# fpga.net
KiCad netlist of a schematic drawn in EAGLE
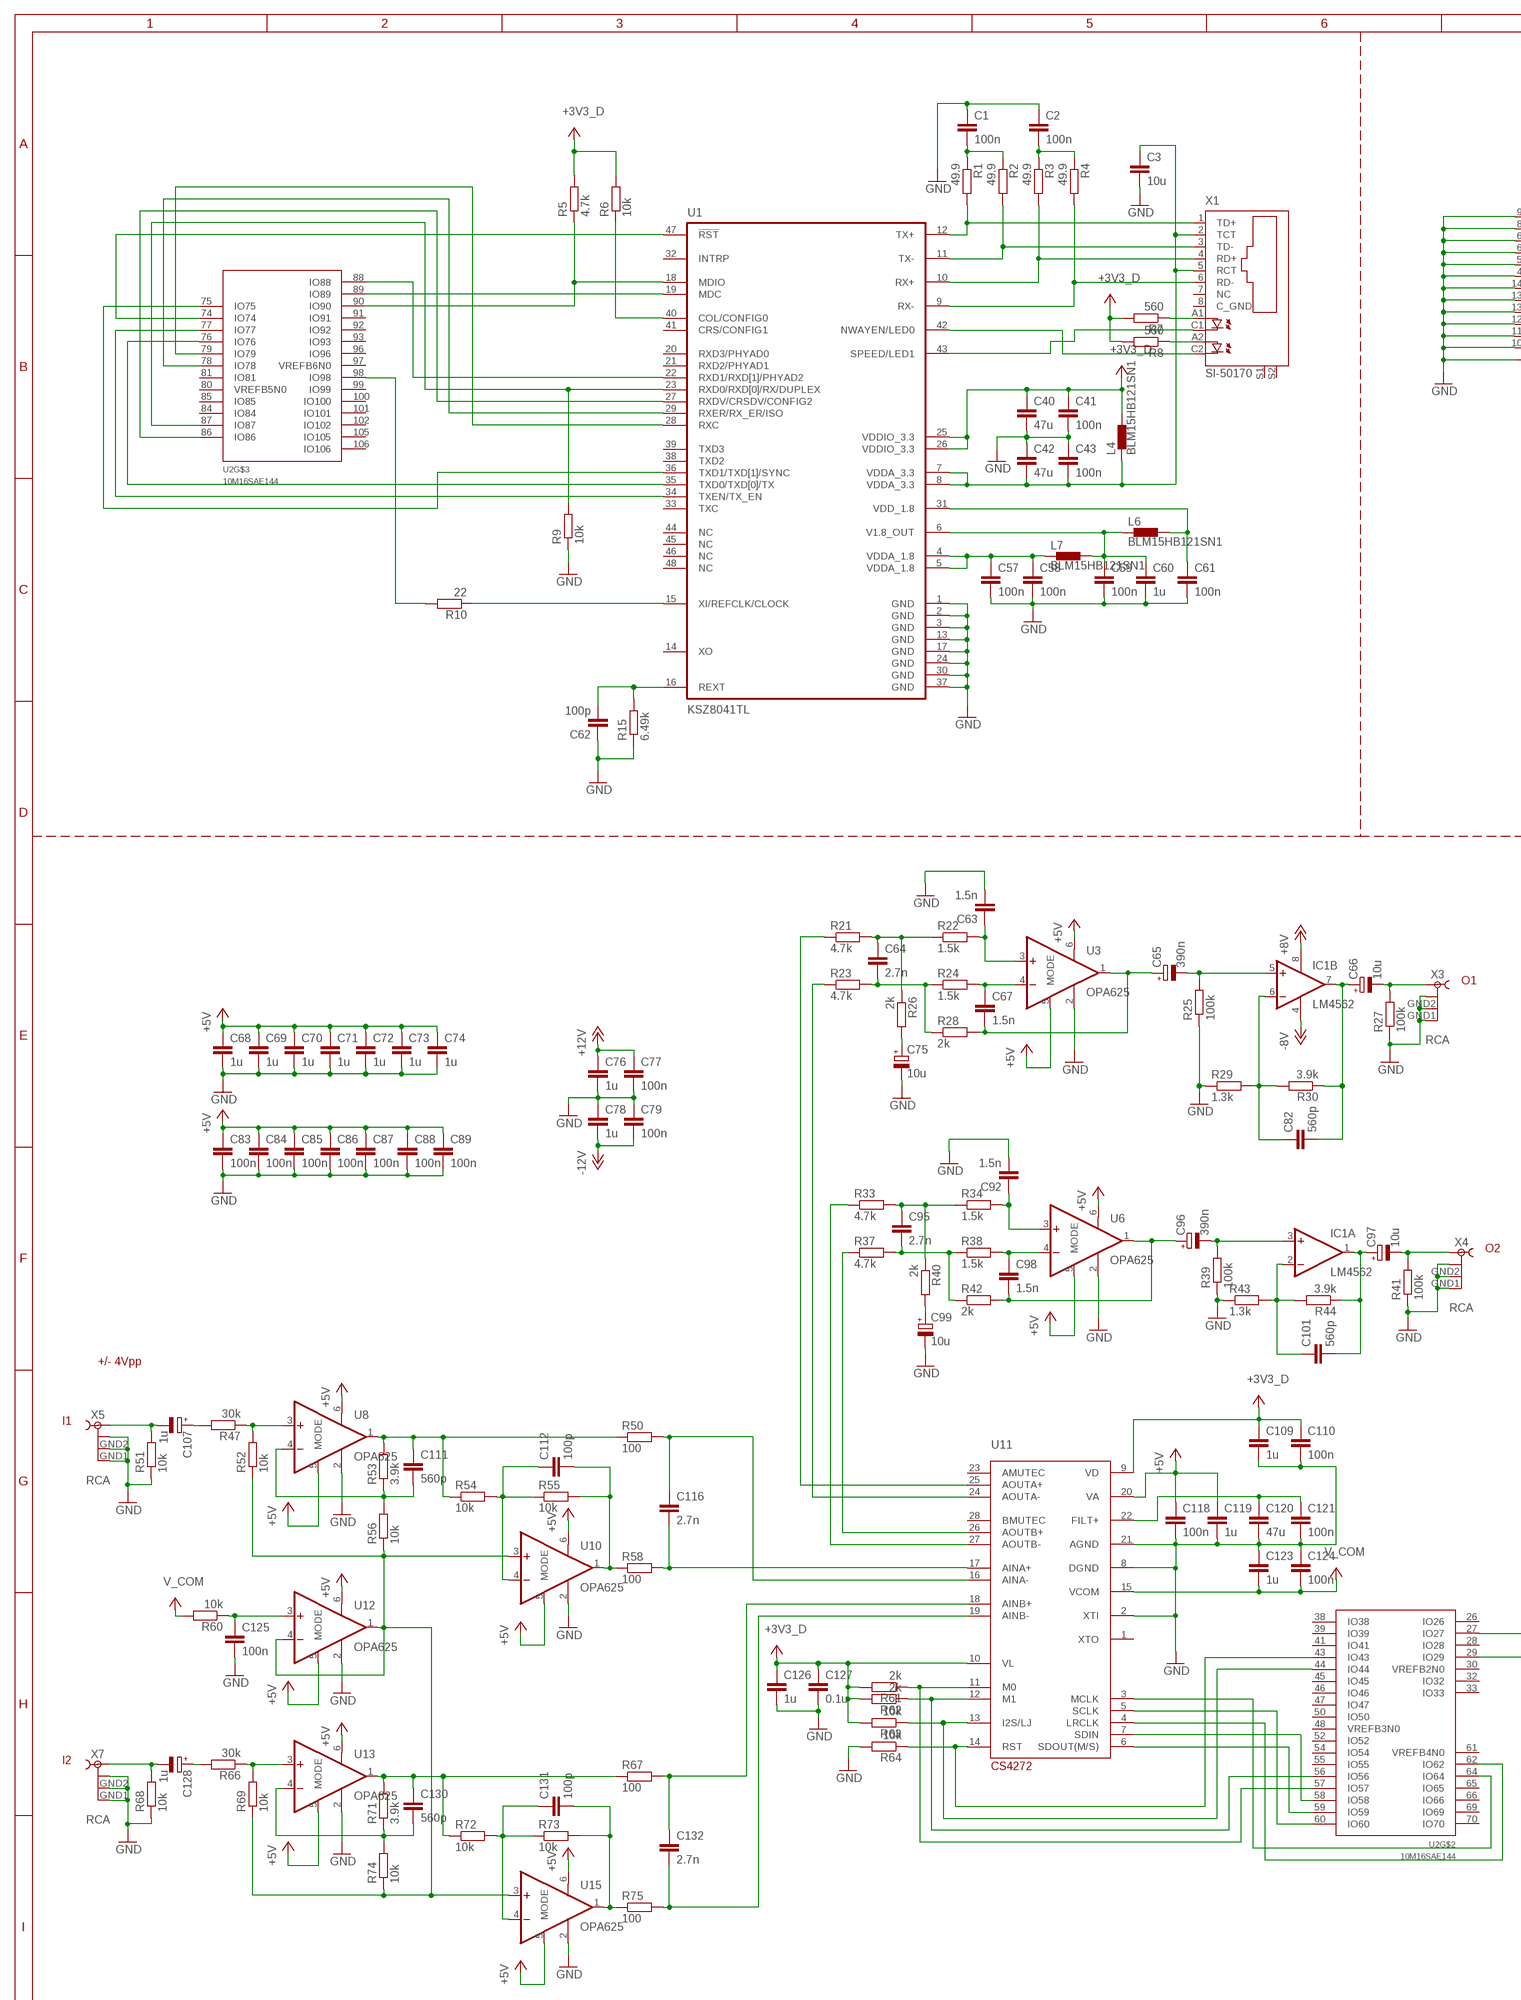
[diagram p0: schematic, sheet 1, part 1 of 2]
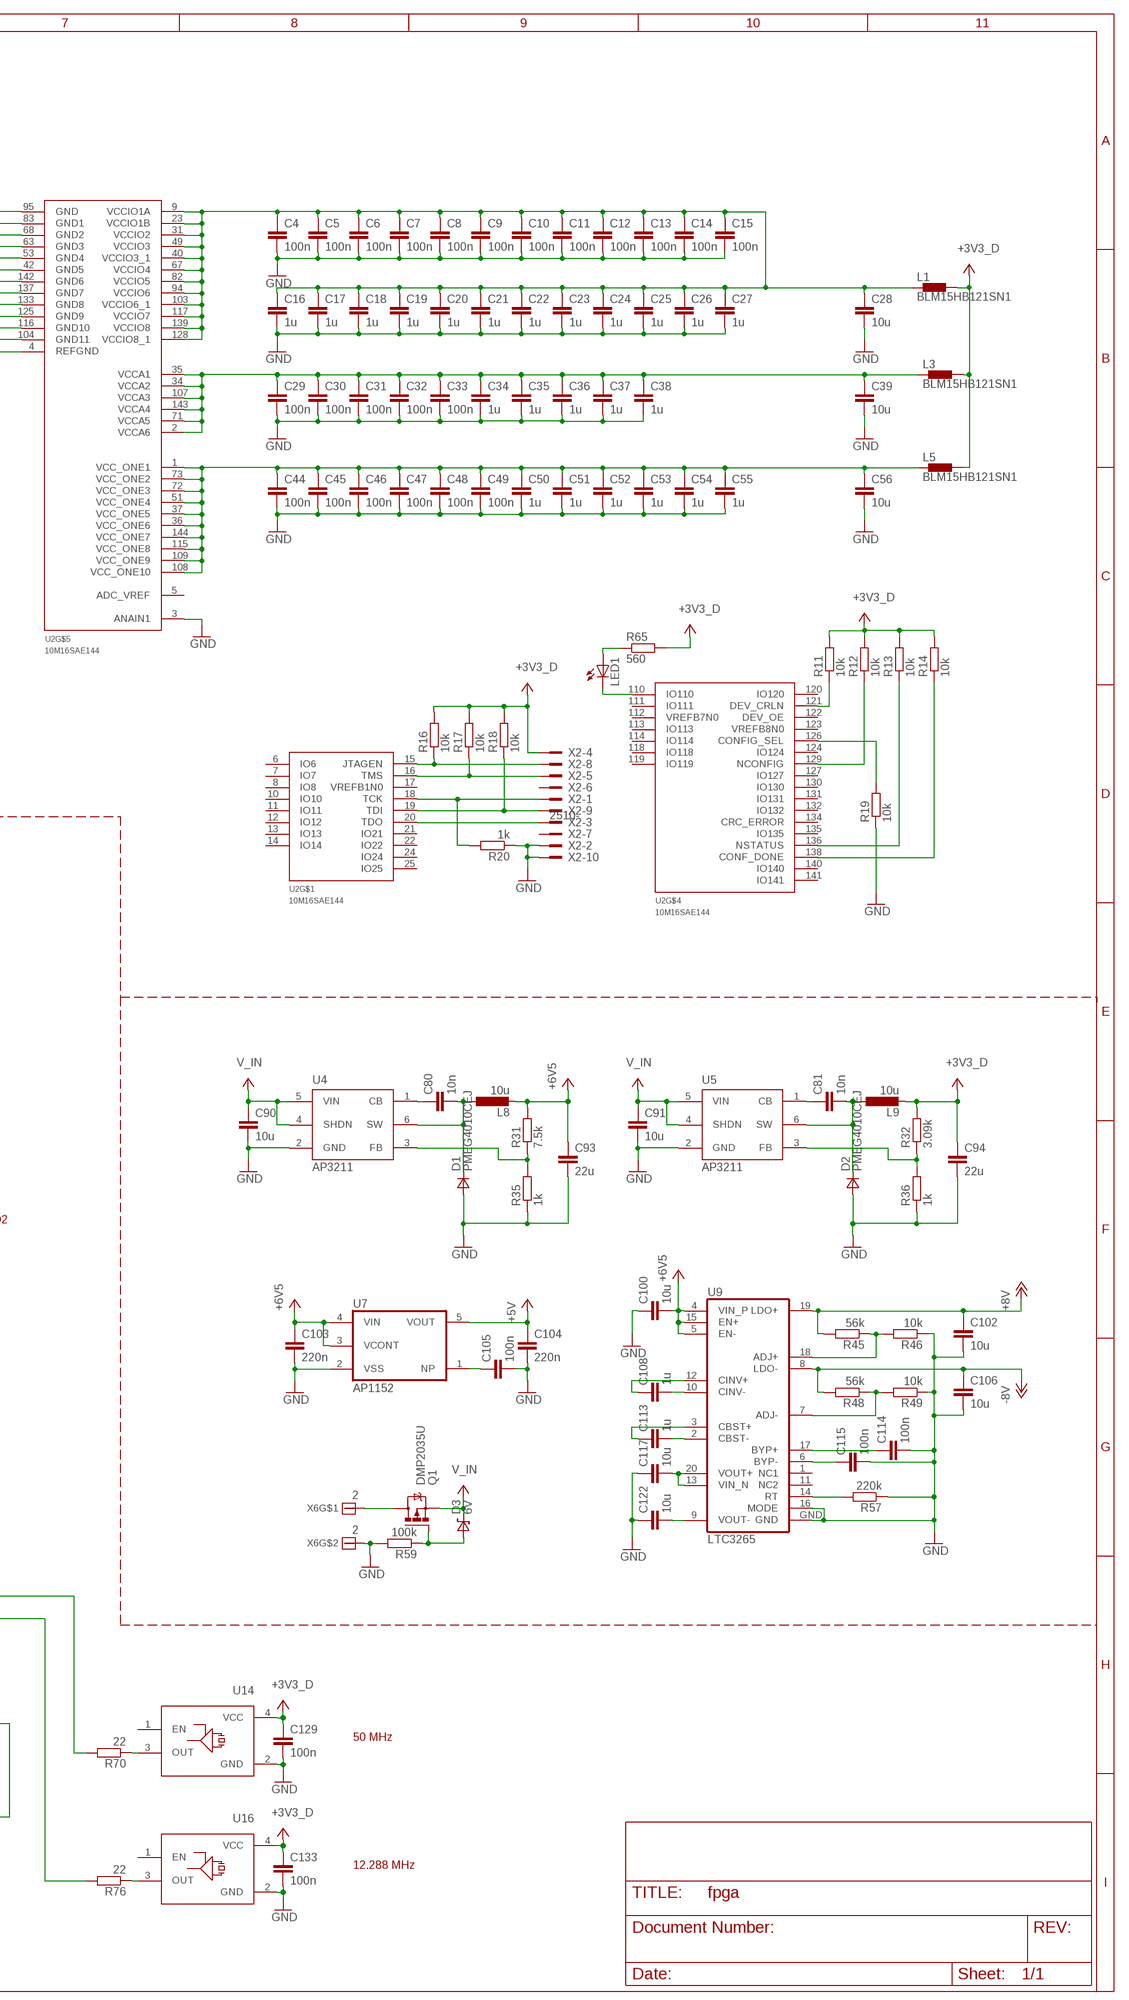
[diagram p1: schematic, sheet 1, part 2 of 2]

(export (version "E")
  (design (tool "Eeschema 10.0.6"))
  (components
    (comp (ref "C1")
      (value "100n")
      (footprint "eagle-import:C0603K")
      (libsource (lib "eagle-import") (part "C-EUC0603K"))
    )
    (comp (ref "C2")
      (value "100n")
      (footprint "eagle-import:C0603K")
      (libsource (lib "eagle-import") (part "C-EUC0603K"))
    )
    (comp (ref "C3")
      (value "10u")
      (footprint "eagle-import:C0805")
      (libsource (lib "eagle-import") (part "C-EUC0805"))
    )
    (comp (ref "C4")
      (value "100n")
      (footprint "eagle-import:C0603K")
      (libsource (lib "eagle-import") (part "C-EUC0603K"))
    )
    (comp (ref "C5")
      (value "100n")
      (footprint "eagle-import:C0603K")
      (libsource (lib "eagle-import") (part "C-EUC0603K"))
    )
    (comp (ref "C6")
      (value "100n")
      (footprint "eagle-import:C0603K")
      (libsource (lib "eagle-import") (part "C-EUC0603K"))
    )
    (comp (ref "C7")
      (value "100n")
      (footprint "eagle-import:C0603K")
      (libsource (lib "eagle-import") (part "C-EUC0603K"))
    )
    (comp (ref "C8")
      (value "100n")
      (footprint "eagle-import:C0603K")
      (libsource (lib "eagle-import") (part "C-EUC0603K"))
    )
    (comp (ref "C9")
      (value "100n")
      (footprint "eagle-import:C0603K")
      (libsource (lib "eagle-import") (part "C-EUC0603K"))
    )
    (comp (ref "C10")
      (value "100n")
      (footprint "eagle-import:C0603K")
      (libsource (lib "eagle-import") (part "C-EUC0603K"))
    )
    (comp (ref "C11")
      (value "100n")
      (footprint "eagle-import:C0603K")
      (libsource (lib "eagle-import") (part "C-EUC0603K"))
    )
    (comp (ref "C12")
      (value "100n")
      (footprint "eagle-import:C0603K")
      (libsource (lib "eagle-import") (part "C-EUC0603K"))
    )
    (comp (ref "C13")
      (value "100n")
      (footprint "eagle-import:C0603K")
      (libsource (lib "eagle-import") (part "C-EUC0603K"))
    )
    (comp (ref "C14")
      (value "100n")
      (footprint "eagle-import:C0603K")
      (libsource (lib "eagle-import") (part "C-EUC0603K"))
    )
    (comp (ref "C15")
      (value "100n")
      (footprint "eagle-import:C0603K")
      (libsource (lib "eagle-import") (part "C-EUC0603K"))
    )
    (comp (ref "C16")
      (value "1u")
      (footprint "eagle-import:C0603K")
      (libsource (lib "eagle-import") (part "C-EUC0603K"))
    )
    (comp (ref "C17")
      (value "1u")
      (footprint "eagle-import:C0603K")
      (libsource (lib "eagle-import") (part "C-EUC0603K"))
    )
    (comp (ref "C18")
      (value "1u")
      (footprint "eagle-import:C0603K")
      (libsource (lib "eagle-import") (part "C-EUC0603K"))
    )
    (comp (ref "C19")
      (value "1u")
      (footprint "eagle-import:C0603K")
      (libsource (lib "eagle-import") (part "C-EUC0603K"))
    )
    (comp (ref "C20")
      (value "1u")
      (footprint "eagle-import:C0603K")
      (libsource (lib "eagle-import") (part "C-EUC0603K"))
    )
    (comp (ref "C21")
      (value "1u")
      (footprint "eagle-import:C0603K")
      (libsource (lib "eagle-import") (part "C-EUC0603K"))
    )
    (comp (ref "C22")
      (value "1u")
      (footprint "eagle-import:C0603K")
      (libsource (lib "eagle-import") (part "C-EUC0603K"))
    )
    (comp (ref "C23")
      (value "1u")
      (footprint "eagle-import:C0603K")
      (libsource (lib "eagle-import") (part "C-EUC0603K"))
    )
    (comp (ref "C24")
      (value "1u")
      (footprint "eagle-import:C0603K")
      (libsource (lib "eagle-import") (part "C-EUC0603K"))
    )
    (comp (ref "C25")
      (value "1u")
      (footprint "eagle-import:C0603K")
      (libsource (lib "eagle-import") (part "C-EUC0603K"))
    )
    (comp (ref "C26")
      (value "1u")
      (footprint "eagle-import:C0603K")
      (libsource (lib "eagle-import") (part "C-EUC0603K"))
    )
    (comp (ref "C27")
      (value "1u")
      (footprint "eagle-import:C0603K")
      (libsource (lib "eagle-import") (part "C-EUC0603K"))
    )
    (comp (ref "C28")
      (value "10u")
      (footprint "eagle-import:C0603K")
      (libsource (lib "eagle-import") (part "C-EUC0603K"))
    )
    (comp (ref "C29")
      (value "100n")
      (footprint "eagle-import:C0603K")
      (libsource (lib "eagle-import") (part "C-EUC0603K"))
    )
    (comp (ref "C30")
      (value "100n")
      (footprint "eagle-import:C0603K")
      (libsource (lib "eagle-import") (part "C-EUC0603K"))
    )
    (comp (ref "C31")
      (value "100n")
      (footprint "eagle-import:C0603K")
      (libsource (lib "eagle-import") (part "C-EUC0603K"))
    )
    (comp (ref "C32")
      (value "100n")
      (footprint "eagle-import:C0603K")
      (libsource (lib "eagle-import") (part "C-EUC0603K"))
    )
    (comp (ref "C33")
      (value "100n")
      (footprint "eagle-import:C0603K")
      (libsource (lib "eagle-import") (part "C-EUC0603K"))
    )
    (comp (ref "C34")
      (value "1u")
      (footprint "eagle-import:C0603K")
      (libsource (lib "eagle-import") (part "C-EUC0603K"))
    )
    (comp (ref "C35")
      (value "1u")
      (footprint "eagle-import:C0603K")
      (libsource (lib "eagle-import") (part "C-EUC0603K"))
    )
    (comp (ref "C36")
      (value "1u")
      (footprint "eagle-import:C0603K")
      (libsource (lib "eagle-import") (part "C-EUC0603K"))
    )
    (comp (ref "C37")
      (value "1u")
      (footprint "eagle-import:C0603K")
      (libsource (lib "eagle-import") (part "C-EUC0603K"))
    )
    (comp (ref "C38")
      (value "1u")
      (footprint "eagle-import:C0603K")
      (libsource (lib "eagle-import") (part "C-EUC0603K"))
    )
    (comp (ref "C39")
      (value "10u")
      (footprint "eagle-import:C0603K")
      (libsource (lib "eagle-import") (part "C-EUC0603K"))
    )
    (comp (ref "C40")
      (value "47u")
      (footprint "eagle-import:C0805")
      (libsource (lib "eagle-import") (part "C-EUC0805"))
    )
    (comp (ref "C41")
      (value "100n")
      (footprint "eagle-import:C0603K")
      (libsource (lib "eagle-import") (part "C-EUC0603K"))
    )
    (comp (ref "C42")
      (value "47u")
      (footprint "eagle-import:C0805")
      (libsource (lib "eagle-import") (part "C-EUC0805"))
    )
    (comp (ref "C43")
      (value "100n")
      (footprint "eagle-import:C0603K")
      (libsource (lib "eagle-import") (part "C-EUC0603K"))
    )
    (comp (ref "C44")
      (value "100n")
      (footprint "eagle-import:C0603K")
      (libsource (lib "eagle-import") (part "C-EUC0603K"))
    )
    (comp (ref "C45")
      (value "100n")
      (footprint "eagle-import:C0603K")
      (libsource (lib "eagle-import") (part "C-EUC0603K"))
    )
    (comp (ref "C46")
      (value "100n")
      (footprint "eagle-import:C0603K")
      (libsource (lib "eagle-import") (part "C-EUC0603K"))
    )
    (comp (ref "C47")
      (value "100n")
      (footprint "eagle-import:C0603K")
      (libsource (lib "eagle-import") (part "C-EUC0603K"))
    )
    (comp (ref "C48")
      (value "100n")
      (footprint "eagle-import:C0603K")
      (libsource (lib "eagle-import") (part "C-EUC0603K"))
    )
    (comp (ref "C49")
      (value "100n")
      (footprint "eagle-import:C0603K")
      (libsource (lib "eagle-import") (part "C-EUC0603K"))
    )
    (comp (ref "C50")
      (value "1u")
      (footprint "eagle-import:C0603K")
      (libsource (lib "eagle-import") (part "C-EUC0603K"))
    )
    (comp (ref "C51")
      (value "1u")
      (footprint "eagle-import:C0603K")
      (libsource (lib "eagle-import") (part "C-EUC0603K"))
    )
    (comp (ref "C52")
      (value "1u")
      (footprint "eagle-import:C0603K")
      (libsource (lib "eagle-import") (part "C-EUC0603K"))
    )
    (comp (ref "C53")
      (value "1u")
      (footprint "eagle-import:C0603K")
      (libsource (lib "eagle-import") (part "C-EUC0603K"))
    )
    (comp (ref "C54")
      (value "1u")
      (footprint "eagle-import:C0603K")
      (libsource (lib "eagle-import") (part "C-EUC0603K"))
    )
    (comp (ref "C55")
      (value "1u")
      (footprint "eagle-import:C0603K")
      (libsource (lib "eagle-import") (part "C-EUC0603K"))
    )
    (comp (ref "C56")
      (value "10u")
      (footprint "eagle-import:C0603K")
      (libsource (lib "eagle-import") (part "C-EUC0603K"))
    )
    (comp (ref "C57")
      (value "100n")
      (footprint "eagle-import:C0603K")
      (libsource (lib "eagle-import") (part "C-EUC0603K"))
    )
    (comp (ref "C58")
      (value "100n")
      (footprint "eagle-import:C0603K")
      (libsource (lib "eagle-import") (part "C-EUC0603K"))
    )
    (comp (ref "C59")
      (value "100n")
      (footprint "eagle-import:C0603K")
      (libsource (lib "eagle-import") (part "C-EUC0603K"))
    )
    (comp (ref "C60")
      (value "1u")
      (footprint "eagle-import:C0603K")
      (libsource (lib "eagle-import") (part "C-EUC0603K"))
    )
    (comp (ref "C61")
      (value "100n")
      (footprint "eagle-import:C0603K")
      (libsource (lib "eagle-import") (part "C-EUC0603K"))
    )
    (comp (ref "C62")
      (value "100p")
      (footprint "eagle-import:C0603K")
      (libsource (lib "eagle-import") (part "C-EUC0603K"))
    )
    (comp (ref "C63")
      (value "1.5n")
      (footprint "eagle-import:C0603K")
      (libsource (lib "eagle-import") (part "C-EUC0603K"))
    )
    (comp (ref "C64")
      (value "2.7n")
      (footprint "eagle-import:C0603K")
      (libsource (lib "eagle-import") (part "C-EUC0603K"))
    )
    (comp (ref "C65")
      (value "390n")
      (footprint "eagle-import:153CLV-0405")
      (libsource (lib "eagle-import") (part "CPOL-EU153CLV-0405"))
    )
    (comp (ref "C66")
      (value "10u")
      (footprint "eagle-import:153CLV-0405")
      (libsource (lib "eagle-import") (part "CPOL-EU153CLV-0405"))
    )
    (comp (ref "C67")
      (value "1.5n")
      (footprint "eagle-import:C0603K")
      (libsource (lib "eagle-import") (part "C-EUC0603K"))
    )
    (comp (ref "C68")
      (value "1u")
      (footprint "eagle-import:C0603K")
      (libsource (lib "eagle-import") (part "C-EUC0603K"))
    )
    (comp (ref "C69")
      (value "1u")
      (footprint "eagle-import:C0603K")
      (libsource (lib "eagle-import") (part "C-EUC0603K"))
    )
    (comp (ref "C70")
      (value "1u")
      (footprint "eagle-import:C0603K")
      (libsource (lib "eagle-import") (part "C-EUC0603K"))
    )
    (comp (ref "C71")
      (value "1u")
      (footprint "eagle-import:C0603K")
      (libsource (lib "eagle-import") (part "C-EUC0603K"))
    )
    (comp (ref "C72")
      (value "1u")
      (footprint "eagle-import:C0603K")
      (libsource (lib "eagle-import") (part "C-EUC0603K"))
    )
    (comp (ref "C73")
      (value "1u")
      (footprint "eagle-import:C0603K")
      (libsource (lib "eagle-import") (part "C-EUC0603K"))
    )
    (comp (ref "C74")
      (value "1u")
      (footprint "eagle-import:C0603K")
      (libsource (lib "eagle-import") (part "C-EUC0603K"))
    )
    (comp (ref "C75")
      (value "10u")
      (footprint "eagle-import:153CLV-0405")
      (libsource (lib "eagle-import") (part "CPOL-EU153CLV-0405"))
    )
    (comp (ref "C76")
      (value "1u")
      (footprint "eagle-import:C0603K")
      (libsource (lib "eagle-import") (part "C-EUC0603K"))
    )
    (comp (ref "C77")
      (value "100n")
      (footprint "eagle-import:C0603K")
      (libsource (lib "eagle-import") (part "C-EUC0603K"))
    )
    (comp (ref "C78")
      (value "1u")
      (footprint "eagle-import:C0603K")
      (libsource (lib "eagle-import") (part "C-EUC0603K"))
    )
    (comp (ref "C79")
      (value "100n")
      (footprint "eagle-import:C0603K")
      (libsource (lib "eagle-import") (part "C-EUC0603K"))
    )
    (comp (ref "C80")
      (value "10n")
      (footprint "eagle-import:C0603K")
      (libsource (lib "eagle-import") (part "C-EUC0603K"))
    )
    (comp (ref "C81")
      (value "10n")
      (footprint "eagle-import:C0603K")
      (libsource (lib "eagle-import") (part "C-EUC0603K"))
    )
    (comp (ref "C82")
      (value "560p")
      (footprint "eagle-import:C0603K")
      (libsource (lib "eagle-import") (part "C-EUC0603K"))
    )
    (comp (ref "C83")
      (value "100n")
      (footprint "eagle-import:C0603K")
      (libsource (lib "eagle-import") (part "C-EUC0603K"))
    )
    (comp (ref "C84")
      (value "100n")
      (footprint "eagle-import:C0603K")
      (libsource (lib "eagle-import") (part "C-EUC0603K"))
    )
    (comp (ref "C85")
      (value "100n")
      (footprint "eagle-import:C0603K")
      (libsource (lib "eagle-import") (part "C-EUC0603K"))
    )
    (comp (ref "C86")
      (value "100n")
      (footprint "eagle-import:C0603K")
      (libsource (lib "eagle-import") (part "C-EUC0603K"))
    )
    (comp (ref "C87")
      (value "100n")
      (footprint "eagle-import:C0603K")
      (libsource (lib "eagle-import") (part "C-EUC0603K"))
    )
    (comp (ref "C88")
      (value "100n")
      (footprint "eagle-import:C0603K")
      (libsource (lib "eagle-import") (part "C-EUC0603K"))
    )
    (comp (ref "C89")
      (value "100n")
      (footprint "eagle-import:C0603K")
      (libsource (lib "eagle-import") (part "C-EUC0603K"))
    )
    (comp (ref "C90")
      (value "10u")
      (footprint "eagle-import:C0805")
      (libsource (lib "eagle-import") (part "C-EUC0805"))
    )
    (comp (ref "C91")
      (value "10u")
      (footprint "eagle-import:C0805")
      (libsource (lib "eagle-import") (part "C-EUC0805"))
    )
    (comp (ref "C92")
      (value "1.5n")
      (footprint "eagle-import:C0603K")
      (libsource (lib "eagle-import") (part "C-EUC0603K"))
    )
    (comp (ref "C93")
      (value "22u")
      (footprint "eagle-import:C1206")
      (libsource (lib "eagle-import") (part "C-EUC1206"))
    )
    (comp (ref "C94")
      (value "22u")
      (footprint "eagle-import:C1206")
      (libsource (lib "eagle-import") (part "C-EUC1206"))
    )
    (comp (ref "C95")
      (value "2.7n")
      (footprint "eagle-import:C0603K")
      (libsource (lib "eagle-import") (part "C-EUC0603K"))
    )
    (comp (ref "C96")
      (value "390n")
      (footprint "eagle-import:153CLV-0405")
      (libsource (lib "eagle-import") (part "CPOL-EU153CLV-0405"))
    )
    (comp (ref "C97")
      (value "10u")
      (footprint "eagle-import:153CLV-0405")
      (libsource (lib "eagle-import") (part "CPOL-EU153CLV-0405"))
    )
    (comp (ref "C98")
      (value "1.5n")
      (footprint "eagle-import:C0603K")
      (libsource (lib "eagle-import") (part "C-EUC0603K"))
    )
    (comp (ref "C99")
      (value "10u")
      (footprint "eagle-import:153CLV-0405")
      (libsource (lib "eagle-import") (part "CPOL-EU153CLV-0405"))
    )
    (comp (ref "C100")
      (value "10u")
      (footprint "eagle-import:C0603K")
      (libsource (lib "eagle-import") (part "C-EUC0603K"))
    )
    (comp (ref "C101")
      (value "560p")
      (footprint "eagle-import:C0603K")
      (libsource (lib "eagle-import") (part "C-EUC0603K"))
    )
    (comp (ref "C102")
      (value "10u")
      (footprint "eagle-import:C0603K")
      (libsource (lib "eagle-import") (part "C-EUC0603K"))
    )
    (comp (ref "C103")
      (value "220n")
      (footprint "eagle-import:C0603K")
      (libsource (lib "eagle-import") (part "C-EUC0603K"))
    )
    (comp (ref "C104")
      (value "220n")
      (footprint "eagle-import:C0603K")
      (libsource (lib "eagle-import") (part "C-EUC0603K"))
    )
    (comp (ref "C105")
      (value "100n")
      (footprint "eagle-import:C0603K")
      (libsource (lib "eagle-import") (part "C-EUC0603K"))
    )
    (comp (ref "C106")
      (value "10u")
      (footprint "eagle-import:C0603K")
      (libsource (lib "eagle-import") (part "C-EUC0603K"))
    )
    (comp (ref "C107")
      (value "1u")
      (footprint "eagle-import:153CLV-0405")
      (libsource (lib "eagle-import") (part "CPOL-EU153CLV-0405"))
    )
    (comp (ref "C108")
      (value "1u")
      (footprint "eagle-import:C0603K")
      (libsource (lib "eagle-import") (part "C-EUC0603K"))
    )
    (comp (ref "C109")
      (value "1u")
      (footprint "eagle-import:C0603K")
      (libsource (lib "eagle-import") (part "C-EUC0603K"))
    )
    (comp (ref "C110")
      (value "100n")
      (footprint "eagle-import:C0603K")
      (libsource (lib "eagle-import") (part "C-EUC0603K"))
    )
    (comp (ref "C111")
      (value "560p")
      (footprint "eagle-import:C0603K")
      (libsource (lib "eagle-import") (part "C-EUC0603K"))
    )
    (comp (ref "C112")
      (value "100p")
      (footprint "eagle-import:C0603K")
      (libsource (lib "eagle-import") (part "C-EUC0603K"))
    )
    (comp (ref "C113")
      (value "1u")
      (footprint "eagle-import:C0603K")
      (libsource (lib "eagle-import") (part "C-EUC0603K"))
    )
    (comp (ref "C114")
      (value "100n")
      (footprint "eagle-import:C0603K")
      (libsource (lib "eagle-import") (part "C-EUC0603K"))
    )
    (comp (ref "C115")
      (value "100n")
      (footprint "eagle-import:C0603K")
      (libsource (lib "eagle-import") (part "C-EUC0603K"))
    )
    (comp (ref "C116")
      (value "2.7n")
      (footprint "eagle-import:C0603K")
      (libsource (lib "eagle-import") (part "C-EUC0603K"))
    )
    (comp (ref "C117")
      (value "10u")
      (footprint "eagle-import:C0603K")
      (libsource (lib "eagle-import") (part "C-EUC0603K"))
    )
    (comp (ref "C118")
      (value "100n")
      (footprint "eagle-import:C0603K")
      (libsource (lib "eagle-import") (part "C-EUC0603K"))
    )
    (comp (ref "C119")
      (value "1u")
      (footprint "eagle-import:C0603K")
      (libsource (lib "eagle-import") (part "C-EUC0603K"))
    )
    (comp (ref "C120")
      (value "47u")
      (footprint "eagle-import:C0805")
      (libsource (lib "eagle-import") (part "C-EUC0805"))
    )
    (comp (ref "C121")
      (value "100n")
      (footprint "eagle-import:C0603K")
      (libsource (lib "eagle-import") (part "C-EUC0603K"))
    )
    (comp (ref "C122")
      (value "10u")
      (footprint "eagle-import:C0603K")
      (libsource (lib "eagle-import") (part "C-EUC0603K"))
    )
    (comp (ref "C123")
      (value "1u")
      (footprint "eagle-import:C0603K")
      (libsource (lib "eagle-import") (part "C-EUC0603K"))
    )
    (comp (ref "C124")
      (value "100n")
      (footprint "eagle-import:C0603K")
      (libsource (lib "eagle-import") (part "C-EUC0603K"))
    )
    (comp (ref "C125")
      (value "100n")
      (footprint "eagle-import:C0603K")
      (libsource (lib "eagle-import") (part "C-EUC0603K"))
    )
    (comp (ref "C126")
      (value "1u")
      (footprint "eagle-import:C0603K")
      (libsource (lib "eagle-import") (part "C-EUC0603K"))
    )
    (comp (ref "C127")
      (value "0.1u")
      (footprint "eagle-import:C0603K")
      (libsource (lib "eagle-import") (part "C-EUC0603K"))
    )
    (comp (ref "C128")
      (value "1u")
      (footprint "eagle-import:153CLV-0405")
      (libsource (lib "eagle-import") (part "CPOL-EU153CLV-0405"))
    )
    (comp (ref "C129")
      (value "100n")
      (footprint "eagle-import:C0603K")
      (libsource (lib "eagle-import") (part "C-EUC0603K"))
    )
    (comp (ref "C130")
      (value "560p")
      (footprint "eagle-import:C0603K")
      (libsource (lib "eagle-import") (part "C-EUC0603K"))
    )
    (comp (ref "C131")
      (value "100p")
      (footprint "eagle-import:C0603K")
      (libsource (lib "eagle-import") (part "C-EUC0603K"))
    )
    (comp (ref "C132")
      (value "2.7n")
      (footprint "eagle-import:C0603K")
      (libsource (lib "eagle-import") (part "C-EUC0603K"))
    )
    (comp (ref "C133")
      (value "100n")
      (footprint "eagle-import:C0603K")
      (libsource (lib "eagle-import") (part "C-EUC0603K"))
    )
    (comp (ref "D1")
      (value "PMEG4010CEJ")
      (footprint "eagle-import:SOD323")
      (fields (field (name "MPN") "CDSOD323-T05C"))
      (libsource (lib "eagle-import") (part "DSOD323"))
    )
    (comp (ref "D2")
      (value "PMEG4010CEJ")
      (footprint "eagle-import:SOD323")
      (fields (field (name "MPN") "CDSOD323-T05C"))
      (libsource (lib "eagle-import") (part "DSOD323"))
    )
    (comp (ref "D3")
      (value "6V")
      (footprint "eagle-import:SOD323")
      (fields (field (name "MPN") "CDSOD323-T05C"))
      (libsource (lib "eagle-import") (part "DSOD323"))
    )
    (comp (ref "IC1")
      (value "LM4562")
      (footprint "eagle-import:SO08")
      (libsource (lib "eagle-import") (part "4558DLM"))
    )
    (comp (ref "L1")
      (value "BLM15HB121SN1")
      (footprint "eagle-import:0402")
      (libsource (lib "eagle-import") (part "BLM15HB121SN1"))
    )
    (comp (ref "L3")
      (value "BLM15HB121SN1")
      (footprint "eagle-import:0402")
      (libsource (lib "eagle-import") (part "BLM15HB121SN1"))
    )
    (comp (ref "L4")
      (value "BLM15HB121SN1")
      (footprint "eagle-import:0402")
      (libsource (lib "eagle-import") (part "BLM15HB121SN1"))
    )
    (comp (ref "L5")
      (value "BLM15HB121SN1")
      (footprint "eagle-import:0402")
      (libsource (lib "eagle-import") (part "BLM15HB121SN1"))
    )
    (comp (ref "L6")
      (value "BLM15HB121SN1")
      (footprint "eagle-import:0402")
      (libsource (lib "eagle-import") (part "BLM15HB121SN1"))
    )
    (comp (ref "L7")
      (value "BLM15HB121SN1")
      (footprint "eagle-import:0402")
      (libsource (lib "eagle-import") (part "BLM15HB121SN1"))
    )
    (comp (ref "L8")
      (value "10u")
      (footprint "eagle-import:AAA")
      (libsource (lib "eagle-import") (part "L-EU"))
    )
    (comp (ref "L9")
      (value "10u")
      (footprint "eagle-import:AAA")
      (libsource (lib "eagle-import") (part "L-EU"))
    )
    (comp (ref "LED1")
      (value "LEDCHIPLED_0603")
      (footprint "eagle-import:CHIPLED_0603")
      (libsource (lib "eagle-import") (part "LEDCHIPLED_0603"))
    )
    (comp (ref "Q1")
      (value "DMP2035U")
      (footprint "eagle-import:MICRO3")
      (libsource (lib "eagle-import") (part "IRLML5203"))
    )
    (comp (ref "R1")
      (value "49.9")
      (footprint "eagle-import:R0603")
      (libsource (lib "eagle-import") (part "R-EU_R0603"))
    )
    (comp (ref "R2")
      (value "49.9")
      (footprint "eagle-import:R0603")
      (libsource (lib "eagle-import") (part "R-EU_R0603"))
    )
    (comp (ref "R3")
      (value "49.9")
      (footprint "eagle-import:R0603")
      (libsource (lib "eagle-import") (part "R-EU_R0603"))
    )
    (comp (ref "R4")
      (value "49.9")
      (footprint "eagle-import:R0603")
      (libsource (lib "eagle-import") (part "R-EU_R0603"))
    )
    (comp (ref "R5")
      (value "4.7k")
      (footprint "eagle-import:R0603")
      (libsource (lib "eagle-import") (part "R-EU_R0603"))
    )
    (comp (ref "R6")
      (value "10k")
      (footprint "eagle-import:R0603")
      (libsource (lib "eagle-import") (part "R-EU_R0603"))
    )
    (comp (ref "R7")
      (value "560")
      (footprint "eagle-import:R0603")
      (libsource (lib "eagle-import") (part "R-EU_R0603"))
    )
    (comp (ref "R8")
      (value "560")
      (footprint "eagle-import:R0603")
      (libsource (lib "eagle-import") (part "R-EU_R0603"))
    )
    (comp (ref "R9")
      (value "10k")
      (footprint "eagle-import:R0603")
      (libsource (lib "eagle-import") (part "R-EU_R0603"))
    )
    (comp (ref "R10")
      (value "22")
      (footprint "eagle-import:R0603")
      (libsource (lib "eagle-import") (part "R-EU_R0603"))
    )
    (comp (ref "R11")
      (value "10k")
      (footprint "eagle-import:R0603")
      (libsource (lib "eagle-import") (part "R-EU_R0603"))
    )
    (comp (ref "R12")
      (value "10k")
      (footprint "eagle-import:R0603")
      (libsource (lib "eagle-import") (part "R-EU_R0603"))
    )
    (comp (ref "R13")
      (value "10k")
      (footprint "eagle-import:R0603")
      (libsource (lib "eagle-import") (part "R-EU_R0603"))
    )
    (comp (ref "R14")
      (value "10k")
      (footprint "eagle-import:R0603")
      (libsource (lib "eagle-import") (part "R-EU_R0603"))
    )
    (comp (ref "R15")
      (value "6.49k")
      (footprint "eagle-import:R0603")
      (libsource (lib "eagle-import") (part "R-EU_R0603"))
    )
    (comp (ref "R16")
      (value "10k")
      (footprint "eagle-import:R0603")
      (libsource (lib "eagle-import") (part "R-EU_R0603"))
    )
    (comp (ref "R17")
      (value "10k")
      (footprint "eagle-import:R0603")
      (libsource (lib "eagle-import") (part "R-EU_R0603"))
    )
    (comp (ref "R18")
      (value "10k")
      (footprint "eagle-import:R0603")
      (libsource (lib "eagle-import") (part "R-EU_R0603"))
    )
    (comp (ref "R19")
      (value "10k")
      (footprint "eagle-import:R0603")
      (libsource (lib "eagle-import") (part "R-EU_R0603"))
    )
    (comp (ref "R20")
      (value "1k")
      (footprint "eagle-import:R0603")
      (libsource (lib "eagle-import") (part "R-EU_R0603"))
    )
    (comp (ref "R21")
      (value "4.7k")
      (footprint "eagle-import:R0603")
      (libsource (lib "eagle-import") (part "R-EU_R0603"))
    )
    (comp (ref "R22")
      (value "1.5k")
      (footprint "eagle-import:R0603")
      (libsource (lib "eagle-import") (part "R-EU_R0603"))
    )
    (comp (ref "R23")
      (value "4.7k")
      (footprint "eagle-import:R0603")
      (libsource (lib "eagle-import") (part "R-EU_R0603"))
    )
    (comp (ref "R24")
      (value "1.5k")
      (footprint "eagle-import:R0603")
      (libsource (lib "eagle-import") (part "R-EU_R0603"))
    )
    (comp (ref "R25")
      (value "100k")
      (footprint "eagle-import:R0603")
      (libsource (lib "eagle-import") (part "R-EU_R0603"))
    )
    (comp (ref "R26")
      (value "2k")
      (footprint "eagle-import:R0603")
      (libsource (lib "eagle-import") (part "R-EU_R0603"))
    )
    (comp (ref "R27")
      (value "100k")
      (footprint "eagle-import:R0603")
      (libsource (lib "eagle-import") (part "R-EU_R0603"))
    )
    (comp (ref "R28")
      (value "2k")
      (footprint "eagle-import:R0603")
      (libsource (lib "eagle-import") (part "R-EU_R0603"))
    )
    (comp (ref "R29")
      (value "1.3k")
      (footprint "eagle-import:R0603")
      (libsource (lib "eagle-import") (part "R-EU_R0603"))
    )
    (comp (ref "R30")
      (value "3.9k")
      (footprint "eagle-import:R0603")
      (libsource (lib "eagle-import") (part "R-EU_R0603"))
    )
    (comp (ref "R31")
      (value "7.5k")
      (footprint "eagle-import:R0603")
      (libsource (lib "eagle-import") (part "R-EU_R0603"))
    )
    (comp (ref "R32")
      (value "3.09k")
      (footprint "eagle-import:R0603")
      (libsource (lib "eagle-import") (part "R-EU_R0603"))
    )
    (comp (ref "R33")
      (value "4.7k")
      (footprint "eagle-import:R0603")
      (libsource (lib "eagle-import") (part "R-EU_R0603"))
    )
    (comp (ref "R34")
      (value "1.5k")
      (footprint "eagle-import:R0603")
      (libsource (lib "eagle-import") (part "R-EU_R0603"))
    )
    (comp (ref "R35")
      (value "1k")
      (footprint "eagle-import:R0603")
      (libsource (lib "eagle-import") (part "R-EU_R0603"))
    )
    (comp (ref "R36")
      (value "1k")
      (footprint "eagle-import:R0603")
      (libsource (lib "eagle-import") (part "R-EU_R0603"))
    )
    (comp (ref "R37")
      (value "4.7k")
      (footprint "eagle-import:R0603")
      (libsource (lib "eagle-import") (part "R-EU_R0603"))
    )
    (comp (ref "R38")
      (value "1.5k")
      (footprint "eagle-import:R0603")
      (libsource (lib "eagle-import") (part "R-EU_R0603"))
    )
    (comp (ref "R39")
      (value "100k")
      (footprint "eagle-import:R0603")
      (libsource (lib "eagle-import") (part "R-EU_R0603"))
    )
    (comp (ref "R40")
      (value "2k")
      (footprint "eagle-import:R0603")
      (libsource (lib "eagle-import") (part "R-EU_R0603"))
    )
    (comp (ref "R41")
      (value "100k")
      (footprint "eagle-import:R0603")
      (libsource (lib "eagle-import") (part "R-EU_R0603"))
    )
    (comp (ref "R42")
      (value "2k")
      (footprint "eagle-import:R0603")
      (libsource (lib "eagle-import") (part "R-EU_R0603"))
    )
    (comp (ref "R43")
      (value "1.3k")
      (footprint "eagle-import:R0603")
      (libsource (lib "eagle-import") (part "R-EU_R0603"))
    )
    (comp (ref "R44")
      (value "3.9k")
      (footprint "eagle-import:R0603")
      (libsource (lib "eagle-import") (part "R-EU_R0603"))
    )
    (comp (ref "R45")
      (value "56k")
      (footprint "eagle-import:R0603")
      (libsource (lib "eagle-import") (part "R-EU_R0603"))
    )
    (comp (ref "R46")
      (value "10k")
      (footprint "eagle-import:R0603")
      (libsource (lib "eagle-import") (part "R-EU_R0603"))
    )
    (comp (ref "R47")
      (value "30k")
      (footprint "eagle-import:R0603")
      (libsource (lib "eagle-import") (part "R-EU_R0603"))
    )
    (comp (ref "R48")
      (value "56k")
      (footprint "eagle-import:R0603")
      (libsource (lib "eagle-import") (part "R-EU_R0603"))
    )
    (comp (ref "R49")
      (value "10k")
      (footprint "eagle-import:R0603")
      (libsource (lib "eagle-import") (part "R-EU_R0603"))
    )
    (comp (ref "R50")
      (value "100")
      (footprint "eagle-import:R0603")
      (libsource (lib "eagle-import") (part "R-EU_R0603"))
    )
    (comp (ref "R51")
      (value "10k")
      (footprint "eagle-import:R0603")
      (libsource (lib "eagle-import") (part "R-EU_R0603"))
    )
    (comp (ref "R52")
      (value "10k")
      (footprint "eagle-import:R0603")
      (libsource (lib "eagle-import") (part "R-EU_R0603"))
    )
    (comp (ref "R53")
      (value "3.9k")
      (footprint "eagle-import:R0603")
      (libsource (lib "eagle-import") (part "R-EU_R0603"))
    )
    (comp (ref "R54")
      (value "10k")
      (footprint "eagle-import:R0603")
      (libsource (lib "eagle-import") (part "R-EU_R0603"))
    )
    (comp (ref "R55")
      (value "10k")
      (footprint "eagle-import:R0603")
      (libsource (lib "eagle-import") (part "R-EU_R0603"))
    )
    (comp (ref "R56")
      (value "10k")
      (footprint "eagle-import:R0603")
      (libsource (lib "eagle-import") (part "R-EU_R0603"))
    )
    (comp (ref "R57")
      (value "220k")
      (footprint "eagle-import:R0603")
      (libsource (lib "eagle-import") (part "R-EU_R0603"))
    )
    (comp (ref "R58")
      (value "100")
      (footprint "eagle-import:R0603")
      (libsource (lib "eagle-import") (part "R-EU_R0603"))
    )
    (comp (ref "R59")
      (value "100k")
      (footprint "eagle-import:R0603")
      (libsource (lib "eagle-import") (part "R-EU_R0603"))
    )
    (comp (ref "R60")
      (value "10k")
      (footprint "eagle-import:R0603")
      (libsource (lib "eagle-import") (part "R-EU_R0603"))
    )
    (comp (ref "R61")
      (value "2k")
      (footprint "eagle-import:R0603")
      (libsource (lib "eagle-import") (part "R-EU_R0603"))
    )
    (comp (ref "R62")
      (value "2k")
      (footprint "eagle-import:R0603")
      (libsource (lib "eagle-import") (part "R-EU_R0603"))
    )
    (comp (ref "R63")
      (value "10k")
      (footprint "eagle-import:R0603")
      (libsource (lib "eagle-import") (part "R-EU_R0603"))
    )
    (comp (ref "R64")
      (value "10k")
      (footprint "eagle-import:R0603")
      (libsource (lib "eagle-import") (part "R-EU_R0603"))
    )
    (comp (ref "R65")
      (value "560")
      (footprint "eagle-import:R0603")
      (libsource (lib "eagle-import") (part "R-EU_R0603"))
    )
    (comp (ref "R66")
      (value "30k")
      (footprint "eagle-import:R0603")
      (libsource (lib "eagle-import") (part "R-EU_R0603"))
    )
    (comp (ref "R67")
      (value "100")
      (footprint "eagle-import:R0603")
      (libsource (lib "eagle-import") (part "R-EU_R0603"))
    )
    (comp (ref "R68")
      (value "10k")
      (footprint "eagle-import:R0603")
      (libsource (lib "eagle-import") (part "R-EU_R0603"))
    )
    (comp (ref "R69")
      (value "10k")
      (footprint "eagle-import:R0603")
      (libsource (lib "eagle-import") (part "R-EU_R0603"))
    )
    (comp (ref "R70")
      (value "22")
      (footprint "eagle-import:R0603")
      (libsource (lib "eagle-import") (part "R-EU_R0603"))
    )
    (comp (ref "R71")
      (value "3.9k")
      (footprint "eagle-import:R0603")
      (libsource (lib "eagle-import") (part "R-EU_R0603"))
    )
    (comp (ref "R72")
      (value "10k")
      (footprint "eagle-import:R0603")
      (libsource (lib "eagle-import") (part "R-EU_R0603"))
    )
    (comp (ref "R73")
      (value "10k")
      (footprint "eagle-import:R0603")
      (libsource (lib "eagle-import") (part "R-EU_R0603"))
    )
    (comp (ref "R74")
      (value "10k")
      (footprint "eagle-import:R0603")
      (libsource (lib "eagle-import") (part "R-EU_R0603"))
    )
    (comp (ref "R75")
      (value "100")
      (footprint "eagle-import:R0603")
      (libsource (lib "eagle-import") (part "R-EU_R0603"))
    )
    (comp (ref "R76")
      (value "22")
      (footprint "eagle-import:R0603")
      (libsource (lib "eagle-import") (part "R-EU_R0603"))
    )
    (comp (ref "U1")
      (value "KSZ8041TL")
      (footprint "eagle-import:TQFP48")
      (libsource (lib "eagle-import") (part "KSZ8041TL"))
    )
    (comp (ref "U2")
      (value "10M16SAE144")
      (footprint "eagle-import:EQFP144")
      (libsource (lib "eagle-import") (part "10M16SAE144"))
    )
    (comp (ref "U3")
      (value "OPA625")
      (footprint "eagle-import:SOT23-6")
      (libsource (lib "eagle-import") (part "OPA625"))
    )
    (comp (ref "U4")
      (value "AP3211")
      (footprint "eagle-import:TSOT23-6_DDC")
      (libsource (lib "eagle-import") (part "LMR14205"))
    )
    (comp (ref "U5")
      (value "AP3211")
      (footprint "eagle-import:TSOT23-6_DDC")
      (libsource (lib "eagle-import") (part "LMR14205"))
    )
    (comp (ref "U6")
      (value "OPA625")
      (footprint "eagle-import:SOT23-6")
      (libsource (lib "eagle-import") (part "OPA625"))
    )
    (comp (ref "U7")
      (value "AP1152")
      (footprint "eagle-import:SOT89-5")
      (libsource (lib "eagle-import") (part "AP1152"))
    )
    (comp (ref "U8")
      (value "OPA625")
      (footprint "eagle-import:SOT23-6")
      (libsource (lib "eagle-import") (part "OPA625"))
    )
    (comp (ref "U9")
      (value "LTC3265")
      (footprint "eagle-import:TSSOP20_GND")
      (libsource (lib "eagle-import") (part "LTC3265"))
    )
    (comp (ref "U10")
      (value "OPA625")
      (footprint "eagle-import:SOT23-6")
      (libsource (lib "eagle-import") (part "OPA625"))
    )
    (comp (ref "U11")
      (value "CS4272")
      (footprint "eagle-import:TSSOP28")
      (libsource (lib "eagle-import") (part "CS4272"))
    )
    (comp (ref "U12")
      (value "OPA625")
      (footprint "eagle-import:SOT23-6")
      (libsource (lib "eagle-import") (part "OPA625"))
    )
    (comp (ref "U13")
      (value "OPA625")
      (footprint "eagle-import:SOT23-6")
      (libsource (lib "eagle-import") (part "OPA625"))
    )
    (comp (ref "U14")
      (value "49.152MHz")
      (footprint "eagle-import:OSC")
      (libsource (lib "eagle-import") (part "LFSPXO009686"))
    )
    (comp (ref "U15")
      (value "OPA625")
      (footprint "eagle-import:SOT23-6")
      (libsource (lib "eagle-import") (part "OPA625"))
    )
    (comp (ref "U16")
      (value "50MHz")
      (footprint "eagle-import:OSC")
      (libsource (lib "eagle-import") (part "LFSPXO009686"))
    )
    (comp (ref "X1")
      (value "SI-50170")
      (footprint "eagle-import:SI-50170")
      (libsource (lib "eagle-import") (part "SI-50170"))
    )
    (comp (ref "X2")
      (value "2510-")
      (footprint "eagle-import:PAK100_2500-10")
      (fields (field (name "MF") "3M") (field (name "MPN") "2510-6002UB"))
      (libsource (lib "eagle-import") (part "2510-"))
    )
    (comp (ref "X3")
      (value "RCA")
      (footprint "eagle-import:RCA")
      (libsource (lib "eagle-import") (part "RCA"))
    )
    (comp (ref "X4")
      (value "RCA")
      (footprint "eagle-import:RCA")
      (libsource (lib "eagle-import") (part "RCA"))
    )
    (comp (ref "X5")
      (value "RCA")
      (footprint "eagle-import:RCA")
      (libsource (lib "eagle-import") (part "RCA"))
    )
    (comp (ref "X6") (value "2") (footprint "eagle-import:2") (libsource (lib "eagle-import") (part "2")))
    (comp (ref "X7")
      (value "RCA")
      (footprint "eagle-import:RCA")
      (libsource (lib "eagle-import") (part "RCA"))
    )
  )
  (nets
    (net (code "1") (name "+3V3_D") (class "Default")
      (node (ref "C109") (pin "1") (pinfunction "1_1") (pintype "passive"))
      (node (ref "C110") (pin "1") (pinfunction "1_1") (pintype "passive"))
      (node (ref "C126") (pin "1") (pinfunction "1_1") (pintype "passive"))
      (node (ref "C127") (pin "1") (pinfunction "1_1") (pintype "passive"))
      (node (ref "C129") (pin "1") (pinfunction "1_1") (pintype "passive"))
      (node (ref "C133") (pin "1") (pinfunction "1_1") (pintype "passive"))
      (node (ref "C40") (pin "1") (pinfunction "1_1") (pintype "passive"))
      (node (ref "C41") (pin "1") (pinfunction "1_1") (pintype "passive"))
      (node (ref "C94") (pin "1") (pinfunction "1_1") (pintype "passive"))
      (node (ref "L1") (pin "2") (pinfunction "2_2") (pintype "passive"))
      (node (ref "L3") (pin "2") (pinfunction "2_2") (pintype "passive"))
      (node (ref "L4") (pin "2") (pinfunction "2_2") (pintype "passive"))
      (node (ref "L5") (pin "2") (pinfunction "2_2") (pintype "passive"))
      (node (ref "L9") (pin "P$2") (pinfunction "2_P$2") (pintype "passive"))
      (node (ref "R11") (pin "2") (pinfunction "2_2") (pintype "passive"))
      (node (ref "R12") (pin "2") (pinfunction "2_2") (pintype "passive"))
      (node (ref "R13") (pin "2") (pinfunction "2_2") (pintype "passive"))
      (node (ref "R14") (pin "2") (pinfunction "2_2") (pintype "passive"))
      (node (ref "R16") (pin "2") (pinfunction "2_2") (pintype "passive"))
      (node (ref "R17") (pin "2") (pinfunction "2_2") (pintype "passive"))
      (node (ref "R18") (pin "2") (pinfunction "2_2") (pintype "passive"))
      (node (ref "R32") (pin "2") (pinfunction "2_2") (pintype "passive"))
      (node (ref "R5") (pin "2") (pinfunction "2_2") (pintype "passive"))
      (node (ref "R6") (pin "2") (pinfunction "2_2") (pintype "passive"))
      (node (ref "R61") (pin "2") (pinfunction "2_2") (pintype "passive"))
      (node (ref "R62") (pin "2") (pinfunction "2_2") (pintype "passive"))
      (node (ref "R63") (pin "2") (pinfunction "2_2") (pintype "passive"))
      (node (ref "R65") (pin "2") (pinfunction "2_2") (pintype "passive"))
      (node (ref "R7") (pin "2") (pinfunction "2_2") (pintype "passive"))
      (node (ref "R8") (pin "2") (pinfunction "2_2") (pintype "passive"))
      (node (ref "U1") (pin "25") (pinfunction "VDDIO_3.3_25") (pintype "power_in"))
      (node (ref "U1") (pin "26") (pinfunction "VDDIO_3.3_26") (pintype "power_in"))
      (node (ref "U11") (pin "10") (pinfunction "VL_10") (pintype "bidirectional"))
      (node (ref "U11") (pin "9") (pinfunction "VD_9") (pintype "bidirectional"))
      (node (ref "U14") (pin "4") (pinfunction "VCC_4") (pintype "bidirectional"))
      (node (ref "U16") (pin "4") (pinfunction "VCC_4") (pintype "bidirectional"))
      (node (ref "X2") (pin "4") (pinfunction "KL_4") (pintype "passive"))
    )
    (net (code "2") (name "+5V") (class "Default")
      (node (ref "C104") (pin "1") (pinfunction "1_1") (pintype "passive"))
      (node (ref "C118") (pin "1") (pinfunction "1_1") (pintype "passive"))
      (node (ref "C119") (pin "1") (pinfunction "1_1") (pintype "passive"))
      (node (ref "C68") (pin "1") (pinfunction "1_1") (pintype "passive"))
      (node (ref "C69") (pin "1") (pinfunction "1_1") (pintype "passive"))
      (node (ref "C70") (pin "1") (pinfunction "1_1") (pintype "passive"))
      (node (ref "C71") (pin "1") (pinfunction "1_1") (pintype "passive"))
      (node (ref "C72") (pin "1") (pinfunction "1_1") (pintype "passive"))
      (node (ref "C73") (pin "1") (pinfunction "1_1") (pintype "passive"))
      (node (ref "C74") (pin "1") (pinfunction "1_1") (pintype "passive"))
      (node (ref "C83") (pin "1") (pinfunction "1_1") (pintype "passive"))
      (node (ref "C84") (pin "1") (pinfunction "1_1") (pintype "passive"))
      (node (ref "C85") (pin "1") (pinfunction "1_1") (pintype "passive"))
      (node (ref "C86") (pin "1") (pinfunction "1_1") (pintype "passive"))
      (node (ref "C87") (pin "1") (pinfunction "1_1") (pintype "passive"))
      (node (ref "C88") (pin "1") (pinfunction "1_1") (pintype "passive"))
      (node (ref "C89") (pin "1") (pinfunction "1_1") (pintype "passive"))
      (node (ref "U10") (pin "5") (pinfunction "MODE_5") (pintype "bidirectional"))
      (node (ref "U10") (pin "6") (pinfunction "V+_6") (pintype "power_in"))
      (node (ref "U11") (pin "20") (pinfunction "VA_20") (pintype "bidirectional"))
      (node (ref "U12") (pin "5") (pinfunction "MODE_5") (pintype "bidirectional"))
      (node (ref "U12") (pin "6") (pinfunction "V+_6") (pintype "power_in"))
      (node (ref "U13") (pin "5") (pinfunction "MODE_5") (pintype "bidirectional"))
      (node (ref "U13") (pin "6") (pinfunction "V+_6") (pintype "power_in"))
      (node (ref "U15") (pin "5") (pinfunction "MODE_5") (pintype "bidirectional"))
      (node (ref "U15") (pin "6") (pinfunction "V+_6") (pintype "power_in"))
      (node (ref "U3") (pin "5") (pinfunction "MODE_5") (pintype "bidirectional"))
      (node (ref "U3") (pin "6") (pinfunction "V+_6") (pintype "power_in"))
      (node (ref "U6") (pin "5") (pinfunction "MODE_5") (pintype "bidirectional"))
      (node (ref "U6") (pin "6") (pinfunction "V+_6") (pintype "power_in"))
      (node (ref "U7") (pin "5") (pinfunction "VOUT_5") (pintype "passive"))
      (node (ref "U8") (pin "5") (pinfunction "MODE_5") (pintype "bidirectional"))
      (node (ref "U8") (pin "6") (pinfunction "V+_6") (pintype "power_in"))
    )
    (net (code "3") (name "+6V5") (class "Default")
      (node (ref "C100") (pin "2") (pinfunction "2_2") (pintype "passive"))
      (node (ref "C103") (pin "1") (pinfunction "1_1") (pintype "passive"))
      (node (ref "C93") (pin "1") (pinfunction "1_1") (pintype "passive"))
      (node (ref "L8") (pin "P$2") (pinfunction "2_P$2") (pintype "passive"))
      (node (ref "R31") (pin "2") (pinfunction "2_2") (pintype "passive"))
      (node (ref "U7") (pin "3") (pinfunction "VCONT_3") (pintype "input"))
      (node (ref "U7") (pin "4") (pinfunction "VIN_4") (pintype "input"))
      (node (ref "U9") (pin "15") (pinfunction "EN+_15") (pintype "tri_state"))
      (node (ref "U9") (pin "4") (pinfunction "VIN_P_4") (pintype "passive"))
      (node (ref "U9") (pin "5") (pinfunction "EN-_5") (pintype "input"))
    )
    (net (code "4") (name "+12V") (class "Default")
      (node (ref "C102") (pin "1") (pinfunction "1_1") (pintype "passive"))
      (node (ref "C76") (pin "1") (pinfunction "1_1") (pintype "passive"))
      (node (ref "C77") (pin "1") (pinfunction "1_1") (pintype "passive"))
      (node (ref "IC1") (pin "8") (pinfunction "V+_8") (pintype "power_in"))
      (node (ref "R45") (pin "2") (pinfunction "2_2") (pintype "passive"))
      (node (ref "U9") (pin "19") (pinfunction "LDO+_19") (pintype "tri_state"))
    )
    (net (code "5") (name "-12V") (class "Default")
      (node (ref "C106") (pin "1") (pinfunction "1_1") (pintype "passive"))
      (node (ref "C78") (pin "2") (pinfunction "2_2") (pintype "passive"))
      (node (ref "C79") (pin "2") (pinfunction "2_2") (pintype "passive"))
      (node (ref "IC1") (pin "4") (pinfunction "V-_4") (pintype "power_in"))
      (node (ref "R48") (pin "2") (pinfunction "2_2") (pintype "passive"))
      (node (ref "U9") (pin "8") (pinfunction "LDO-_8") (pintype "tri_state"))
    )
    (net (code "6") (name "GND") (class "Default")
      (node (ref "C1") (pin "1") (pinfunction "1_1") (pintype "passive"))
      (node (ref "C10") (pin "2") (pinfunction "2_2") (pintype "passive"))
      (node (ref "C100") (pin "1") (pinfunction "1_1") (pintype "passive"))
      (node (ref "C102") (pin "2") (pinfunction "2_2") (pintype "passive"))
      (node (ref "C103") (pin "2") (pinfunction "2_2") (pintype "passive"))
      (node (ref "C104") (pin "2") (pinfunction "2_2") (pintype "passive"))
      (node (ref "C105") (pin "2") (pinfunction "2_2") (pintype "passive"))
      (node (ref "C106") (pin "2") (pinfunction "2_2") (pintype "passive"))
      (node (ref "C109") (pin "2") (pinfunction "2_2") (pintype "passive"))
      (node (ref "C11") (pin "2") (pinfunction "2_2") (pintype "passive"))
      (node (ref "C110") (pin "2") (pinfunction "2_2") (pintype "passive"))
      (node (ref "C114") (pin "2") (pinfunction "2_2") (pintype "passive"))
      (node (ref "C115") (pin "2") (pinfunction "2_2") (pintype "passive"))
      (node (ref "C117") (pin "1") (pinfunction "1_1") (pintype "passive"))
      (node (ref "C118") (pin "2") (pinfunction "2_2") (pintype "passive"))
      (node (ref "C119") (pin "2") (pinfunction "2_2") (pintype "passive"))
      (node (ref "C12") (pin "2") (pinfunction "2_2") (pintype "passive"))
      (node (ref "C120") (pin "2") (pinfunction "2_2") (pintype "passive"))
      (node (ref "C121") (pin "2") (pinfunction "2_2") (pintype "passive"))
      (node (ref "C122") (pin "1") (pinfunction "1_1") (pintype "passive"))
      (node (ref "C123") (pin "1") (pinfunction "1_1") (pintype "passive"))
      (node (ref "C124") (pin "1") (pinfunction "1_1") (pintype "passive"))
      (node (ref "C125") (pin "2") (pinfunction "2_2") (pintype "passive"))
      (node (ref "C126") (pin "2") (pinfunction "2_2") (pintype "passive"))
      (node (ref "C127") (pin "2") (pinfunction "2_2") (pintype "passive"))
      (node (ref "C129") (pin "2") (pinfunction "2_2") (pintype "passive"))
      (node (ref "C13") (pin "2") (pinfunction "2_2") (pintype "passive"))
      (node (ref "C133") (pin "2") (pinfunction "2_2") (pintype "passive"))
      (node (ref "C14") (pin "2") (pinfunction "2_2") (pintype "passive"))
      (node (ref "C15") (pin "2") (pinfunction "2_2") (pintype "passive"))
      (node (ref "C16") (pin "2") (pinfunction "2_2") (pintype "passive"))
      (node (ref "C17") (pin "2") (pinfunction "2_2") (pintype "passive"))
      (node (ref "C18") (pin "2") (pinfunction "2_2") (pintype "passive"))
      (node (ref "C19") (pin "2") (pinfunction "2_2") (pintype "passive"))
      (node (ref "C2") (pin "1") (pinfunction "1_1") (pintype "passive"))
      (node (ref "C20") (pin "2") (pinfunction "2_2") (pintype "passive"))
      (node (ref "C21") (pin "2") (pinfunction "2_2") (pintype "passive"))
      (node (ref "C22") (pin "2") (pinfunction "2_2") (pintype "passive"))
      (node (ref "C23") (pin "2") (pinfunction "2_2") (pintype "passive"))
      (node (ref "C24") (pin "2") (pinfunction "2_2") (pintype "passive"))
      (node (ref "C25") (pin "2") (pinfunction "2_2") (pintype "passive"))
      (node (ref "C26") (pin "2") (pinfunction "2_2") (pintype "passive"))
      (node (ref "C27") (pin "2") (pinfunction "2_2") (pintype "passive"))
      (node (ref "C28") (pin "2") (pinfunction "2_2") (pintype "passive"))
      (node (ref "C29") (pin "2") (pinfunction "2_2") (pintype "passive"))
      (node (ref "C3") (pin "2") (pinfunction "2_2") (pintype "passive"))
      (node (ref "C30") (pin "2") (pinfunction "2_2") (pintype "passive"))
      (node (ref "C31") (pin "2") (pinfunction "2_2") (pintype "passive"))
      (node (ref "C32") (pin "2") (pinfunction "2_2") (pintype "passive"))
      (node (ref "C33") (pin "2") (pinfunction "2_2") (pintype "passive"))
      (node (ref "C34") (pin "2") (pinfunction "2_2") (pintype "passive"))
      (node (ref "C35") (pin "2") (pinfunction "2_2") (pintype "passive"))
      (node (ref "C36") (pin "2") (pinfunction "2_2") (pintype "passive"))
      (node (ref "C37") (pin "2") (pinfunction "2_2") (pintype "passive"))
      (node (ref "C38") (pin "2") (pinfunction "2_2") (pintype "passive"))
      (node (ref "C39") (pin "2") (pinfunction "2_2") (pintype "passive"))
      (node (ref "C4") (pin "2") (pinfunction "2_2") (pintype "passive"))
      (node (ref "C40") (pin "2") (pinfunction "2_2") (pintype "passive"))
      (node (ref "C41") (pin "2") (pinfunction "2_2") (pintype "passive"))
      (node (ref "C42") (pin "1") (pinfunction "1_1") (pintype "passive"))
      (node (ref "C43") (pin "1") (pinfunction "1_1") (pintype "passive"))
      (node (ref "C44") (pin "2") (pinfunction "2_2") (pintype "passive"))
      (node (ref "C45") (pin "2") (pinfunction "2_2") (pintype "passive"))
      (node (ref "C46") (pin "2") (pinfunction "2_2") (pintype "passive"))
      (node (ref "C47") (pin "2") (pinfunction "2_2") (pintype "passive"))
      (node (ref "C48") (pin "2") (pinfunction "2_2") (pintype "passive"))
      (node (ref "C49") (pin "2") (pinfunction "2_2") (pintype "passive"))
      (node (ref "C5") (pin "2") (pinfunction "2_2") (pintype "passive"))
      (node (ref "C50") (pin "2") (pinfunction "2_2") (pintype "passive"))
      (node (ref "C51") (pin "2") (pinfunction "2_2") (pintype "passive"))
      (node (ref "C52") (pin "2") (pinfunction "2_2") (pintype "passive"))
      (node (ref "C53") (pin "2") (pinfunction "2_2") (pintype "passive"))
      (node (ref "C54") (pin "2") (pinfunction "2_2") (pintype "passive"))
      (node (ref "C55") (pin "2") (pinfunction "2_2") (pintype "passive"))
      (node (ref "C56") (pin "2") (pinfunction "2_2") (pintype "passive"))
      (node (ref "C57") (pin "2") (pinfunction "2_2") (pintype "passive"))
      (node (ref "C58") (pin "2") (pinfunction "2_2") (pintype "passive"))
      (node (ref "C59") (pin "2") (pinfunction "2_2") (pintype "passive"))
      (node (ref "C6") (pin "2") (pinfunction "2_2") (pintype "passive"))
      (node (ref "C60") (pin "2") (pinfunction "2_2") (pintype "passive"))
      (node (ref "C61") (pin "2") (pinfunction "2_2") (pintype "passive"))
      (node (ref "C62") (pin "1") (pinfunction "1_1") (pintype "passive"))
      (node (ref "C63") (pin "2") (pinfunction "2_2") (pintype "passive"))
      (node (ref "C68") (pin "2") (pinfunction "2_2") (pintype "passive"))
      (node (ref "C69") (pin "2") (pinfunction "2_2") (pintype "passive"))
      (node (ref "C7") (pin "2") (pinfunction "2_2") (pintype "passive"))
      (node (ref "C70") (pin "2") (pinfunction "2_2") (pintype "passive"))
      (node (ref "C71") (pin "2") (pinfunction "2_2") (pintype "passive"))
      (node (ref "C72") (pin "2") (pinfunction "2_2") (pintype "passive"))
      (node (ref "C73") (pin "2") (pinfunction "2_2") (pintype "passive"))
      (node (ref "C74") (pin "2") (pinfunction "2_2") (pintype "passive"))
      (node (ref "C75") (pin "-") (pinfunction "-_-") (pintype "passive"))
      (node (ref "C76") (pin "2") (pinfunction "2_2") (pintype "passive"))
      (node (ref "C77") (pin "2") (pinfunction "2_2") (pintype "passive"))
      (node (ref "C78") (pin "1") (pinfunction "1_1") (pintype "passive"))
      (node (ref "C79") (pin "1") (pinfunction "1_1") (pintype "passive"))
      (node (ref "C8") (pin "2") (pinfunction "2_2") (pintype "passive"))
      (node (ref "C83") (pin "2") (pinfunction "2_2") (pintype "passive"))
      (node (ref "C84") (pin "2") (pinfunction "2_2") (pintype "passive"))
      (node (ref "C85") (pin "2") (pinfunction "2_2") (pintype "passive"))
      (node (ref "C86") (pin "2") (pinfunction "2_2") (pintype "passive"))
      (node (ref "C87") (pin "2") (pinfunction "2_2") (pintype "passive"))
      (node (ref "C88") (pin "2") (pinfunction "2_2") (pintype "passive"))
      (node (ref "C89") (pin "2") (pinfunction "2_2") (pintype "passive"))
      (node (ref "C9") (pin "2") (pinfunction "2_2") (pintype "passive"))
      (node (ref "C90") (pin "2") (pinfunction "2_2") (pintype "passive"))
      (node (ref "C91") (pin "2") (pinfunction "2_2") (pintype "passive"))
      (node (ref "C92") (pin "2") (pinfunction "2_2") (pintype "passive"))
      (node (ref "C93") (pin "2") (pinfunction "2_2") (pintype "passive"))
      (node (ref "C94") (pin "2") (pinfunction "2_2") (pintype "passive"))
      (node (ref "C99") (pin "-") (pinfunction "-_-") (pintype "passive"))
      (node (ref "D1") (pin "2") (pinfunction "A_2") (pintype "passive"))
      (node (ref "D2") (pin "2") (pinfunction "A_2") (pintype "passive"))
      (node (ref "R15") (pin "1") (pinfunction "1_1") (pintype "passive"))
      (node (ref "R19") (pin "1") (pinfunction "1_1") (pintype "passive"))
      (node (ref "R20") (pin "1") (pinfunction "1_1") (pintype "passive"))
      (node (ref "R25") (pin "1") (pinfunction "1_1") (pintype "passive"))
      (node (ref "R27") (pin "1") (pinfunction "1_1") (pintype "passive"))
      (node (ref "R29") (pin "1") (pinfunction "1_1") (pintype "passive"))
      (node (ref "R35") (pin "1") (pinfunction "1_1") (pintype "passive"))
      (node (ref "R36") (pin "1") (pinfunction "1_1") (pintype "passive"))
      (node (ref "R39") (pin "1") (pinfunction "1_1") (pintype "passive"))
      (node (ref "R41") (pin "1") (pinfunction "1_1") (pintype "passive"))
      (node (ref "R43") (pin "1") (pinfunction "1_1") (pintype "passive"))
      (node (ref "R46") (pin "1") (pinfunction "1_1") (pintype "passive"))
      (node (ref "R49") (pin "1") (pinfunction "1_1") (pintype "passive"))
      (node (ref "R51") (pin "1") (pinfunction "1_1") (pintype "passive"))
      (node (ref "R57") (pin "1") (pinfunction "1_1") (pintype "passive"))
      (node (ref "R59") (pin "2") (pinfunction "2_2") (pintype "passive"))
      (node (ref "R64") (pin "2") (pinfunction "2_2") (pintype "passive"))
      (node (ref "R68") (pin "1") (pinfunction "1_1") (pintype "passive"))
      (node (ref "R9") (pin "1") (pinfunction "1_1") (pintype "passive"))
      (node (ref "U1") (pin "1") (pinfunction "GND_1") (pintype "power_in"))
      (node (ref "U1") (pin "13") (pinfunction "GND_13") (pintype "power_in"))
      (node (ref "U1") (pin "17") (pinfunction "GND_17") (pintype "power_in"))
      (node (ref "U1") (pin "2") (pinfunction "GND_2") (pintype "power_in"))
      (node (ref "U1") (pin "24") (pinfunction "GND_24") (pintype "power_in"))
      (node (ref "U1") (pin "3") (pinfunction "GND_3") (pintype "power_in"))
      (node (ref "U1") (pin "30") (pinfunction "GND_30") (pintype "power_in"))
      (node (ref "U1") (pin "37") (pinfunction "GND_37") (pintype "power_in"))
      (node (ref "U10") (pin "2") (pinfunction "V-_2") (pintype "power_in"))
      (node (ref "U11") (pin "2") (pinfunction "XTI_2") (pintype "bidirectional"))
      (node (ref "U11") (pin "21") (pinfunction "AGND_21") (pintype "bidirectional"))
      (node (ref "U11") (pin "8") (pinfunction "DGND_8") (pintype "bidirectional"))
      (node (ref "U12") (pin "2") (pinfunction "V-_2") (pintype "power_in"))
      (node (ref "U13") (pin "2") (pinfunction "V-_2") (pintype "power_in"))
      (node (ref "U14") (pin "2") (pinfunction "GND_2") (pintype "bidirectional"))
      (node (ref "U15") (pin "2") (pinfunction "V-_2") (pintype "power_in"))
      (node (ref "U16") (pin "2") (pinfunction "GND_2") (pintype "bidirectional"))
      (node (ref "U2") (pin "104") (pinfunction "GND11_104") (pintype "bidirectional"))
      (node (ref "U2") (pin "116") (pinfunction "GND10_116") (pintype "bidirectional"))
      (node (ref "U2") (pin "125") (pinfunction "GND9_125") (pintype "bidirectional"))
      (node (ref "U2") (pin "133") (pinfunction "GND8_133") (pintype "bidirectional"))
      (node (ref "U2") (pin "137") (pinfunction "GND7_137") (pintype "bidirectional"))
      (node (ref "U2") (pin "142") (pinfunction "GND6_142") (pintype "bidirectional"))
      (node (ref "U2") (pin "3") (pinfunction "ANAIN1_3") (pintype "bidirectional"))
      (node (ref "U2") (pin "4") (pinfunction "REFGND_4") (pintype "bidirectional"))
      (node (ref "U2") (pin "42") (pinfunction "GND5_42") (pintype "bidirectional"))
      (node (ref "U2") (pin "53") (pinfunction "GND4_53") (pintype "bidirectional"))
      (node (ref "U2") (pin "63") (pinfunction "GND3_63") (pintype "bidirectional"))
      (node (ref "U2") (pin "68") (pinfunction "GND2_68") (pintype "bidirectional"))
      (node (ref "U2") (pin "83") (pinfunction "GND1_83") (pintype "bidirectional"))
      (node (ref "U2") (pin "95") (pinfunction "GND_95") (pintype "bidirectional"))
      (node (ref "U3") (pin "2") (pinfunction "V-_2") (pintype "power_in"))
      (node (ref "U4") (pin "2") (pinfunction "GND_2") (pintype "input"))
      (node (ref "U5") (pin "2") (pinfunction "GND_2") (pintype "input"))
      (node (ref "U6") (pin "2") (pinfunction "V-_2") (pintype "power_in"))
      (node (ref "U7") (pin "2") (pinfunction "VSS_2") (pintype "input"))
      (node (ref "U8") (pin "2") (pinfunction "V-_2") (pintype "power_in"))
      (node (ref "U9") (pin "16") (pinfunction "MODE_16") (pintype "tri_state"))
      (node (ref "U9") (pin "GND") (pinfunction "GND_GND") (pintype "power_in"))
      (node (ref "X2") (pin "10") (pinfunction "KL_10") (pintype "passive"))
      (node (ref "X2") (pin "2") (pinfunction "KL_2") (pintype "passive"))
      (node (ref "X3") (pin "GND1") (pinfunction "4_GND1") (pintype "passive"))
      (node (ref "X3") (pin "GND2") (pinfunction "3_GND2") (pintype "passive"))
      (node (ref "X3") (pin "GND3") (pinfunction "2_GND3") (pintype "passive"))
      (node (ref "X4") (pin "GND1") (pinfunction "4_GND1") (pintype "passive"))
      (node (ref "X4") (pin "GND2") (pinfunction "3_GND2") (pintype "passive"))
      (node (ref "X4") (pin "GND3") (pinfunction "2_GND3") (pintype "passive"))
      (node (ref "X5") (pin "GND1") (pinfunction "4_GND1") (pintype "passive"))
      (node (ref "X5") (pin "GND2") (pinfunction "3_GND2") (pintype "passive"))
      (node (ref "X5") (pin "GND3") (pinfunction "2_GND3") (pintype "passive"))
      (node (ref "X6") (pin "P$2") (pinfunction "1_P$2") (pintype "passive"))
      (node (ref "X7") (pin "GND1") (pinfunction "4_GND1") (pintype "passive"))
      (node (ref "X7") (pin "GND2") (pinfunction "3_GND2") (pintype "passive"))
      (node (ref "X7") (pin "GND3") (pinfunction "2_GND3") (pintype "passive"))
    )
    (net (code "7") (name "Net-(C1-Pad2)") (class "Default")
      (node (ref "C1") (pin "2") (pinfunction "2_2") (pintype "passive"))
      (node (ref "R1") (pin "1") (pinfunction "1_1") (pintype "passive"))
      (node (ref "R2") (pin "1") (pinfunction "1_1") (pintype "passive"))
    )
    (net (code "8") (name "Net-(C2-Pad2)") (class "Default")
      (node (ref "C2") (pin "2") (pinfunction "2_2") (pintype "passive"))
      (node (ref "R3") (pin "1") (pinfunction "1_1") (pintype "passive"))
      (node (ref "R4") (pin "1") (pinfunction "1_1") (pintype "passive"))
    )
    (net (code "9") (name "Net-(C57-Pad1)") (class "Default")
      (node (ref "C57") (pin "1") (pinfunction "1_1") (pintype "passive"))
      (node (ref "C58") (pin "1") (pinfunction "1_1") (pintype "passive"))
      (node (ref "L7") (pin "1") (pinfunction "1_1") (pintype "passive"))
      (node (ref "U1") (pin "4") (pinfunction "VDDA_1.8_4") (pintype "input"))
      (node (ref "U1") (pin "5") (pinfunction "VDDA_1.8_5") (pintype "input"))
    )
    (net (code "10") (name "Net-(C64-Pad1)") (class "Default")
      (node (ref "C64") (pin "1") (pinfunction "1_1") (pintype "passive"))
      (node (ref "R21") (pin "2") (pinfunction "2_2") (pintype "passive"))
      (node (ref "R22") (pin "1") (pinfunction "1_1") (pintype "passive"))
      (node (ref "R26") (pin "1") (pinfunction "1_1") (pintype "passive"))
    )
    (net (code "11") (name "Net-(C64-Pad2)") (class "Default")
      (node (ref "C64") (pin "2") (pinfunction "2_2") (pintype "passive"))
      (node (ref "R23") (pin "2") (pinfunction "2_2") (pintype "passive"))
      (node (ref "R24") (pin "1") (pinfunction "1_1") (pintype "passive"))
      (node (ref "R28") (pin "1") (pinfunction "1_1") (pintype "passive"))
    )
    (net (code "12") (name "Net-(C75-Pad+)") (class "Default")
      (node (ref "C75") (pin "+") (pinfunction "+_+") (pintype "passive"))
      (node (ref "R26") (pin "2") (pinfunction "2_2") (pintype "passive"))
    )
    (net (code "13") (name "Net-(C95-Pad1)") (class "Default")
      (node (ref "C95") (pin "1") (pinfunction "1_1") (pintype "passive"))
      (node (ref "R33") (pin "2") (pinfunction "2_2") (pintype "passive"))
      (node (ref "R34") (pin "1") (pinfunction "1_1") (pintype "passive"))
      (node (ref "R40") (pin "1") (pinfunction "1_1") (pintype "passive"))
    )
    (net (code "14") (name "Net-(C95-Pad2)") (class "Default")
      (node (ref "C95") (pin "2") (pinfunction "2_2") (pintype "passive"))
      (node (ref "R37") (pin "2") (pinfunction "2_2") (pintype "passive"))
      (node (ref "R38") (pin "1") (pinfunction "1_1") (pintype "passive"))
      (node (ref "R42") (pin "1") (pinfunction "1_1") (pintype "passive"))
    )
    (net (code "15") (name "Net-(C99-Pad+)") (class "Default")
      (node (ref "C99") (pin "+") (pinfunction "+_+") (pintype "passive"))
      (node (ref "R40") (pin "2") (pinfunction "2_2") (pintype "passive"))
    )
    (net (code "16") (name "Net-(C107-Pad+)") (class "Default")
      (node (ref "C107") (pin "+") (pinfunction "+_+") (pintype "passive"))
      (node (ref "R47") (pin "2") (pinfunction "2_2") (pintype "passive"))
    )
    (net (code "17") (name "Net-(C128-Pad+)") (class "Default")
      (node (ref "C128") (pin "+") (pinfunction "+_+") (pintype "passive"))
      (node (ref "R66") (pin "2") (pinfunction "2_2") (pintype "passive"))
    )
    (net (code "18") (name "Net-(D1-C)") (class "Default")
      (node (ref "C80") (pin "2") (pinfunction "2_2") (pintype "passive"))
      (node (ref "D1") (pin "1") (pinfunction "C_1") (pintype "passive"))
      (node (ref "L8") (pin "P$1") (pinfunction "1_P$1") (pintype "passive"))
      (node (ref "U4") (pin "6") (pinfunction "SW_6") (pintype "output"))
    )
    (net (code "19") (name "Net-(D2-C)") (class "Default")
      (node (ref "C81") (pin "2") (pinfunction "2_2") (pintype "passive"))
      (node (ref "D2") (pin "1") (pinfunction "C_1") (pintype "passive"))
      (node (ref "L9") (pin "P$1") (pinfunction "1_P$1") (pintype "passive"))
      (node (ref "U5") (pin "6") (pinfunction "SW_6") (pintype "output"))
    )
    (net (code "20") (name "Net-(D3-A)") (class "Default")
      (node (ref "D3") (pin "2") (pinfunction "A_2") (pintype "passive"))
      (node (ref "Q1") (pin "1") (pinfunction "G_1") (pintype "passive"))
      (node (ref "R59") (pin "1") (pinfunction "1_1") (pintype "passive"))
    )
    (net (code "21") (name "Net-(IC1A-+IN)") (class "Default")
      (node (ref "C96") (pin "-") (pinfunction "-_-") (pintype "passive"))
      (node (ref "IC1") (pin "3") (pinfunction "+IN_3") (pintype "input"))
      (node (ref "R39") (pin "2") (pinfunction "2_2") (pintype "passive"))
    )
    (net (code "22") (name "Net-(IC1A--IN)") (class "Default")
      (node (ref "C101") (pin "1") (pinfunction "1_1") (pintype "passive"))
      (node (ref "IC1") (pin "2") (pinfunction "-IN_2") (pintype "input"))
      (node (ref "R43") (pin "2") (pinfunction "2_2") (pintype "passive"))
      (node (ref "R44") (pin "2") (pinfunction "2_2") (pintype "passive"))
    )
    (net (code "23") (name "Net-(IC1A-OUT)") (class "Default")
      (node (ref "C101") (pin "2") (pinfunction "2_2") (pintype "passive"))
      (node (ref "C97") (pin "+") (pinfunction "+_+") (pintype "passive"))
      (node (ref "IC1") (pin "1") (pinfunction "OUT_1") (pintype "output"))
      (node (ref "R44") (pin "1") (pinfunction "1_1") (pintype "passive"))
    )
    (net (code "24") (name "Net-(IC1B-+IN)") (class "Default")
      (node (ref "C65") (pin "-") (pinfunction "-_-") (pintype "passive"))
      (node (ref "IC1") (pin "5") (pinfunction "+IN_5") (pintype "input"))
      (node (ref "R25") (pin "2") (pinfunction "2_2") (pintype "passive"))
    )
    (net (code "25") (name "Net-(IC1B--IN)") (class "Default")
      (node (ref "C82") (pin "1") (pinfunction "1_1") (pintype "passive"))
      (node (ref "IC1") (pin "6") (pinfunction "-IN_6") (pintype "input"))
      (node (ref "R29") (pin "2") (pinfunction "2_2") (pintype "passive"))
      (node (ref "R30") (pin "2") (pinfunction "2_2") (pintype "passive"))
    )
    (net (code "26") (name "Net-(IC1B-OUT)") (class "Default")
      (node (ref "C66") (pin "+") (pinfunction "+_+") (pintype "passive"))
      (node (ref "C82") (pin "2") (pinfunction "2_2") (pintype "passive"))
      (node (ref "IC1") (pin "7") (pinfunction "OUT_7") (pintype "output"))
      (node (ref "R30") (pin "1") (pinfunction "1_1") (pintype "passive"))
    )
    (net (code "27") (name "Net-(LED1-PadA)") (class "Default")
      (node (ref "LED1") (pin "A") (pinfunction "A_A") (pintype "passive"))
      (node (ref "R65") (pin "1") (pinfunction "1_1") (pintype "passive"))
    )
    (net (code "28") (name "Net-(Q1-D)") (class "Default")
      (node (ref "Q1") (pin "3") (pinfunction "D_3") (pintype "passive"))
      (node (ref "X6") (pin "P$1") (pinfunction "1_P$1") (pintype "passive"))
    )
    (net (code "29") (name "Net-(U1-COL{slash}CONFIG0)") (class "Default")
      (node (ref "R6") (pin "1") (pinfunction "1_1") (pintype "passive"))
      (node (ref "U1") (pin "40") (pinfunction "COL/CONFIG0_40") (pintype "bidirectional"))
    )
    (net (code "30") (name "Net-(U1-MDC)") (class "Default")
      (node (ref "U1") (pin "19") (pinfunction "MDC_19") (pintype "input"))
      (node (ref "U2") (pin "89") (pinfunction "IO89_89") (pintype "bidirectional"))
    )
    (net (code "31") (name "Net-(U1-MDIO)") (class "Default")
      (node (ref "R5") (pin "1") (pinfunction "1_1") (pintype "passive"))
      (node (ref "U1") (pin "18") (pinfunction "MDIO_18") (pintype "bidirectional"))
      (node (ref "U2") (pin "90") (pinfunction "IO90_90") (pintype "bidirectional"))
    )
    (net (code "32") (name "Net-(U1-NWAYEN{slash}LED0)") (class "Default")
      (node (ref "U1") (pin "42") (pinfunction "NWAYEN/LED0_42") (pintype "output"))
      (node (ref "X1") (pin "C2") (pinfunction "C1_C2") (pintype "passive"))
    )
    (net (code "33") (name "Net-(U1-REXT)") (class "Default")
      (node (ref "C62") (pin "2") (pinfunction "2_2") (pintype "passive"))
      (node (ref "R15") (pin "2") (pinfunction "2_2") (pintype "passive"))
      (node (ref "U1") (pin "16") (pinfunction "REXT_16") (pintype "passive"))
    )
    (net (code "34") (name "Net-(U1-RX+)") (class "Default")
      (node (ref "R3") (pin "2") (pinfunction "2_2") (pintype "passive"))
      (node (ref "U1") (pin "10") (pinfunction "RX+_10") (pintype "input"))
      (node (ref "X1") (pin "4") (pinfunction "RD+_4") (pintype "passive"))
    )
    (net (code "35") (name "Net-(U1-RX-)") (class "Default")
      (node (ref "R4") (pin "2") (pinfunction "2_2") (pintype "passive"))
      (node (ref "U1") (pin "9") (pinfunction "RX-_9") (pintype "input"))
      (node (ref "X1") (pin "6") (pinfunction "RD-_6") (pintype "passive"))
    )
    (net (code "36") (name "Net-(U1-RXC)") (class "Default")
      (node (ref "U1") (pin "28") (pinfunction "RXC_28") (pintype "output"))
      (node (ref "U2") (pin "79") (pinfunction "IO79_79") (pintype "bidirectional"))
    )
    (net (code "37") (name "Net-(U1-RXD0{slash}RXD[0]{slash}RX{slash}DUPLEX)") (class "Default")
      (node (ref "R9") (pin "2") (pinfunction "2_2") (pintype "passive"))
      (node (ref "U1") (pin "23") (pinfunction "RXD0/RXD[0]/RX/DUPLEX_23") (pintype "bidirectional"))
      (node (ref "U2") (pin "87") (pinfunction "IO87_87") (pintype "bidirectional"))
    )
    (net (code "38") (name "Net-(U1-RXD1{slash}RXD[1]{slash}PHYAD2)") (class "Default")
      (node (ref "U1") (pin "22") (pinfunction "RXD1/RXD[1]/PHYAD2_22") (pintype "bidirectional"))
      (node (ref "U2") (pin "88") (pinfunction "IO88_88") (pintype "bidirectional"))
    )
    (net (code "39") (name "Net-(U1-RXDV{slash}CRSDV{slash}CONFIG2)") (class "Default")
      (node (ref "U1") (pin "27") (pinfunction "RXDV/CRSDV/CONFIG2_27") (pintype "bidirectional"))
      (node (ref "U2") (pin "86") (pinfunction "IO86_86") (pintype "bidirectional"))
    )
    (net (code "40") (name "Net-(U1-RXER{slash}RX_ER{slash}ISO)") (class "Default")
      (node (ref "U1") (pin "29") (pinfunction "RXER/RX_ER/ISO_29") (pintype "bidirectional"))
      (node (ref "U2") (pin "78") (pinfunction "IO78_78") (pintype "bidirectional"))
    )
    (net (code "41") (name "Net-(U1-SPEED{slash}LED1)") (class "Default")
      (node (ref "U1") (pin "43") (pinfunction "SPEED/LED1_43") (pintype "output"))
      (node (ref "X1") (pin "C1") (pinfunction "C_C1") (pintype "passive"))
    )
    (net (code "42") (name "Net-(U1-TX+)") (class "Default")
      (node (ref "R1") (pin "2") (pinfunction "2_2") (pintype "passive"))
      (node (ref "U1") (pin "12") (pinfunction "TX+_12") (pintype "output"))
      (node (ref "X1") (pin "1") (pinfunction "TD+_1") (pintype "passive"))
    )
    (net (code "43") (name "Net-(U1-TX-)") (class "Default")
      (node (ref "R2") (pin "2") (pinfunction "2_2") (pintype "passive"))
      (node (ref "U1") (pin "11") (pinfunction "TX-_11") (pintype "output"))
      (node (ref "X1") (pin "3") (pinfunction "TD-_3") (pintype "passive"))
    )
    (net (code "44") (name "Net-(U1-TXD0{slash}TXD[0]{slash}TX)") (class "Default")
      (node (ref "U1") (pin "35") (pinfunction "TXD0/TXD[0]/TX_35") (pintype "input"))
      (node (ref "U2") (pin "76") (pinfunction "IO76_76") (pintype "bidirectional"))
    )
    (net (code "45") (name "Net-(U1-TXD1{slash}TXD[1]{slash}SYNC)") (class "Default")
      (node (ref "U1") (pin "36") (pinfunction "TXD1/TXD[1]/SYNC_36") (pintype "input"))
      (node (ref "U2") (pin "75") (pinfunction "IO75_75") (pintype "bidirectional"))
    )
    (net (code "46") (name "Net-(U1-TXEN{slash}TX_EN)") (class "Default")
      (node (ref "U1") (pin "34") (pinfunction "TXEN/TX_EN_34") (pintype "input"))
      (node (ref "U2") (pin "77") (pinfunction "IO77_77") (pintype "bidirectional"))
    )
    (net (code "47") (name "Net-(U1-V1.8_OUT)") (class "Default")
      (node (ref "C59") (pin "1") (pinfunction "1_1") (pintype "passive"))
      (node (ref "C60") (pin "1") (pinfunction "1_1") (pintype "passive"))
      (node (ref "L6") (pin "1") (pinfunction "1_1") (pintype "passive"))
      (node (ref "L7") (pin "2") (pinfunction "2_2") (pintype "passive"))
      (node (ref "U1") (pin "6") (pinfunction "V1.8_OUT_6") (pintype "output"))
    )
    (net (code "48") (name "Net-(U1-VDD_1.8)") (class "Default")
      (node (ref "C61") (pin "1") (pinfunction "1_1") (pintype "passive"))
      (node (ref "L6") (pin "2") (pinfunction "2_2") (pintype "passive"))
      (node (ref "U1") (pin "31") (pinfunction "VDD_1.8_31") (pintype "input"))
    )
    (net (code "49") (name "Net-(U1-XI{slash}REFCLK{slash}CLOCK)") (class "Default")
      (node (ref "R10") (pin "1") (pinfunction "1_1") (pintype "passive"))
      (node (ref "U1") (pin "15") (pinfunction "XI/REFCLK/CLOCK_15") (pintype "input"))
    )
    (net (code "50") (name "Net-(U1-~{RST})") (class "Default")
      (node (ref "U1") (pin "47") (pinfunction "~{RST}_47") (pintype "input"))
      (node (ref "U2") (pin "74") (pinfunction "IO74_74") (pintype "bidirectional"))
    )
    (net (code "51") (name "Net-(U2A-JTAGEN)") (class "Default")
      (node (ref "R16") (pin "1") (pinfunction "1_1") (pintype "passive"))
      (node (ref "U2") (pin "15") (pinfunction "JTAGEN_15") (pintype "bidirectional"))
      (node (ref "X2") (pin "8") (pinfunction "KL_8") (pintype "passive"))
    )
    (net (code "52") (name "Net-(U2A-TCK)") (class "Default")
      (node (ref "R20") (pin "2") (pinfunction "2_2") (pintype "passive"))
      (node (ref "U2") (pin "18") (pinfunction "TCK_18") (pintype "bidirectional"))
      (node (ref "X2") (pin "1") (pinfunction "KL_1") (pintype "passive"))
    )
    (net (code "53") (name "Net-(U2A-TDI)") (class "Default")
      (node (ref "R18") (pin "1") (pinfunction "1_1") (pintype "passive"))
      (node (ref "U2") (pin "19") (pinfunction "TDI_19") (pintype "bidirectional"))
      (node (ref "X2") (pin "9") (pinfunction "KL_9") (pintype "passive"))
    )
    (net (code "54") (name "Net-(U2A-TDO)") (class "Default")
      (node (ref "U2") (pin "20") (pinfunction "TDO_20") (pintype "bidirectional"))
      (node (ref "X2") (pin "3") (pinfunction "KL_3") (pintype "passive"))
    )
    (net (code "55") (name "Net-(U2A-TMS)") (class "Default")
      (node (ref "R17") (pin "1") (pinfunction "1_1") (pintype "passive"))
      (node (ref "U2") (pin "16") (pinfunction "TMS_16") (pintype "bidirectional"))
      (node (ref "X2") (pin "5") (pinfunction "KL_5") (pintype "passive"))
    )
    (net (code "56") (name "Net-(U2B-IO27)") (class "Default")
      (node (ref "R70") (pin "2") (pinfunction "2_2") (pintype "passive"))
      (node (ref "U2") (pin "27") (pinfunction "IO27_27") (pintype "bidirectional"))
    )
    (net (code "57") (name "Net-(U2B-IO29)") (class "Default")
      (node (ref "R76") (pin "2") (pinfunction "2_2") (pintype "passive"))
      (node (ref "U2") (pin "29") (pinfunction "IO29_29") (pintype "bidirectional"))
    )
    (net (code "58") (name "Net-(U2C-IO98)") (class "Default")
      (node (ref "R10") (pin "2") (pinfunction "2_2") (pintype "passive"))
      (node (ref "U2") (pin "98") (pinfunction "IO98_98") (pintype "bidirectional"))
    )
    (net (code "59") (name "Net-(U2D-CONFIG_SEL)") (class "Default")
      (node (ref "R19") (pin "2") (pinfunction "2_2") (pintype "passive"))
      (node (ref "U2") (pin "126") (pinfunction "CONFIG_SEL_126") (pintype "bidirectional"))
    )
    (net (code "60") (name "Net-(U2D-CONF_DONE)") (class "Default")
      (node (ref "R14") (pin "1") (pinfunction "1_1") (pintype "passive"))
      (node (ref "U2") (pin "138") (pinfunction "CONF_DONE_138") (pintype "bidirectional"))
    )
    (net (code "61") (name "Net-(U2D-DEV_CRLN)") (class "Default")
      (node (ref "R11") (pin "1") (pinfunction "1_1") (pintype "passive"))
      (node (ref "U2") (pin "121") (pinfunction "DEV_CRLN_121") (pintype "bidirectional"))
    )
    (net (code "62") (name "Net-(U2D-IO110)") (class "Default")
      (node (ref "LED1") (pin "C") (pinfunction "C_C") (pintype "passive"))
      (node (ref "U2") (pin "110") (pinfunction "IO110_110") (pintype "bidirectional"))
    )
    (net (code "63") (name "Net-(U2D-NCONFIG)") (class "Default")
      (node (ref "R12") (pin "1") (pinfunction "1_1") (pintype "passive"))
      (node (ref "U2") (pin "129") (pinfunction "NCONFIG_129") (pintype "bidirectional"))
    )
    (net (code "64") (name "Net-(U2D-NSTATUS)") (class "Default")
      (node (ref "R13") (pin "1") (pinfunction "1_1") (pintype "passive"))
      (node (ref "U2") (pin "136") (pinfunction "NSTATUS_136") (pintype "bidirectional"))
    )
    (net (code "65") (name "Net-(U2E-VCCA1)") (class "Default")
      (node (ref "C29") (pin "1") (pinfunction "1_1") (pintype "passive"))
      (node (ref "C30") (pin "1") (pinfunction "1_1") (pintype "passive"))
      (node (ref "C31") (pin "1") (pinfunction "1_1") (pintype "passive"))
      (node (ref "C32") (pin "1") (pinfunction "1_1") (pintype "passive"))
      (node (ref "C33") (pin "1") (pinfunction "1_1") (pintype "passive"))
      (node (ref "C34") (pin "1") (pinfunction "1_1") (pintype "passive"))
      (node (ref "C35") (pin "1") (pinfunction "1_1") (pintype "passive"))
      (node (ref "C36") (pin "1") (pinfunction "1_1") (pintype "passive"))
      (node (ref "C37") (pin "1") (pinfunction "1_1") (pintype "passive"))
      (node (ref "C38") (pin "1") (pinfunction "1_1") (pintype "passive"))
      (node (ref "C39") (pin "1") (pinfunction "1_1") (pintype "passive"))
      (node (ref "L3") (pin "1") (pinfunction "1_1") (pintype "passive"))
      (node (ref "U2") (pin "107") (pinfunction "VCCA3_107") (pintype "bidirectional"))
      (node (ref "U2") (pin "143") (pinfunction "VCCA4_143") (pintype "bidirectional"))
      (node (ref "U2") (pin "2") (pinfunction "VCCA6_2") (pintype "bidirectional"))
      (node (ref "U2") (pin "34") (pinfunction "VCCA2_34") (pintype "bidirectional"))
      (node (ref "U2") (pin "35") (pinfunction "VCCA1_35") (pintype "bidirectional"))
      (node (ref "U2") (pin "71") (pinfunction "VCCA5_71") (pintype "bidirectional"))
    )
    (net (code "66") (name "Net-(U2E-VCCIO1A)") (class "Default")
      (node (ref "C10") (pin "1") (pinfunction "1_1") (pintype "passive"))
      (node (ref "C11") (pin "1") (pinfunction "1_1") (pintype "passive"))
      (node (ref "C12") (pin "1") (pinfunction "1_1") (pintype "passive"))
      (node (ref "C13") (pin "1") (pinfunction "1_1") (pintype "passive"))
      (node (ref "C14") (pin "1") (pinfunction "1_1") (pintype "passive"))
      (node (ref "C15") (pin "1") (pinfunction "1_1") (pintype "passive"))
      (node (ref "C16") (pin "1") (pinfunction "1_1") (pintype "passive"))
      (node (ref "C17") (pin "1") (pinfunction "1_1") (pintype "passive"))
      (node (ref "C18") (pin "1") (pinfunction "1_1") (pintype "passive"))
      (node (ref "C19") (pin "1") (pinfunction "1_1") (pintype "passive"))
      (node (ref "C20") (pin "1") (pinfunction "1_1") (pintype "passive"))
      (node (ref "C21") (pin "1") (pinfunction "1_1") (pintype "passive"))
      (node (ref "C22") (pin "1") (pinfunction "1_1") (pintype "passive"))
      (node (ref "C23") (pin "1") (pinfunction "1_1") (pintype "passive"))
      (node (ref "C24") (pin "1") (pinfunction "1_1") (pintype "passive"))
      (node (ref "C25") (pin "1") (pinfunction "1_1") (pintype "passive"))
      (node (ref "C26") (pin "1") (pinfunction "1_1") (pintype "passive"))
      (node (ref "C27") (pin "1") (pinfunction "1_1") (pintype "passive"))
      (node (ref "C28") (pin "1") (pinfunction "1_1") (pintype "passive"))
      (node (ref "C4") (pin "1") (pinfunction "1_1") (pintype "passive"))
      (node (ref "C5") (pin "1") (pinfunction "1_1") (pintype "passive"))
      (node (ref "C6") (pin "1") (pinfunction "1_1") (pintype "passive"))
      (node (ref "C7") (pin "1") (pinfunction "1_1") (pintype "passive"))
      (node (ref "C8") (pin "1") (pinfunction "1_1") (pintype "passive"))
      (node (ref "C9") (pin "1") (pinfunction "1_1") (pintype "passive"))
      (node (ref "L1") (pin "1") (pinfunction "1_1") (pintype "passive"))
      (node (ref "U2") (pin "103") (pinfunction "VCCIO6_1_103") (pintype "bidirectional"))
      (node (ref "U2") (pin "117") (pinfunction "VCCIO7_117") (pintype "bidirectional"))
      (node (ref "U2") (pin "128") (pinfunction "VCCIO8_1_128") (pintype "bidirectional"))
      (node (ref "U2") (pin "139") (pinfunction "VCCIO8_139") (pintype "bidirectional"))
      (node (ref "U2") (pin "23") (pinfunction "VCCIO1B_23") (pintype "bidirectional"))
      (node (ref "U2") (pin "31") (pinfunction "VCCIO2_31") (pintype "bidirectional"))
      (node (ref "U2") (pin "40") (pinfunction "VCCIO3_1_40") (pintype "bidirectional"))
      (node (ref "U2") (pin "49") (pinfunction "VCCIO3_49") (pintype "bidirectional"))
      (node (ref "U2") (pin "67") (pinfunction "VCCIO4_67") (pintype "bidirectional"))
      (node (ref "U2") (pin "82") (pinfunction "VCCIO5_82") (pintype "bidirectional"))
      (node (ref "U2") (pin "9") (pinfunction "VCCIO1A_9") (pintype "bidirectional"))
      (node (ref "U2") (pin "94") (pinfunction "VCCIO6_94") (pintype "bidirectional"))
    )
    (net (code "67") (name "Net-(U2E-VCC_ONE1)") (class "Default")
      (node (ref "C44") (pin "1") (pinfunction "1_1") (pintype "passive"))
      (node (ref "C45") (pin "1") (pinfunction "1_1") (pintype "passive"))
      (node (ref "C46") (pin "1") (pinfunction "1_1") (pintype "passive"))
      (node (ref "C47") (pin "1") (pinfunction "1_1") (pintype "passive"))
      (node (ref "C48") (pin "1") (pinfunction "1_1") (pintype "passive"))
      (node (ref "C49") (pin "1") (pinfunction "1_1") (pintype "passive"))
      (node (ref "C50") (pin "1") (pinfunction "1_1") (pintype "passive"))
      (node (ref "C51") (pin "1") (pinfunction "1_1") (pintype "passive"))
      (node (ref "C52") (pin "1") (pinfunction "1_1") (pintype "passive"))
      (node (ref "C53") (pin "1") (pinfunction "1_1") (pintype "passive"))
      (node (ref "C54") (pin "1") (pinfunction "1_1") (pintype "passive"))
      (node (ref "C55") (pin "1") (pinfunction "1_1") (pintype "passive"))
      (node (ref "C56") (pin "1") (pinfunction "1_1") (pintype "passive"))
      (node (ref "L5") (pin "1") (pinfunction "1_1") (pintype "passive"))
      (node (ref "U2") (pin "1") (pinfunction "VCC_ONE1_1") (pintype "bidirectional"))
      (node (ref "U2") (pin "108") (pinfunction "VCC_ONE10_108") (pintype "bidirectional"))
      (node (ref "U2") (pin "109") (pinfunction "VCC_ONE9_109") (pintype "bidirectional"))
      (node (ref "U2") (pin "115") (pinfunction "VCC_ONE8_115") (pintype "bidirectional"))
      (node (ref "U2") (pin "144") (pinfunction "VCC_ONE7_144") (pintype "bidirectional"))
      (node (ref "U2") (pin "36") (pinfunction "VCC_ONE6_36") (pintype "bidirectional"))
      (node (ref "U2") (pin "37") (pinfunction "VCC_ONE5_37") (pintype "bidirectional"))
      (node (ref "U2") (pin "51") (pinfunction "VCC_ONE4_51") (pintype "bidirectional"))
      (node (ref "U2") (pin "72") (pinfunction "VCC_ONE3_72") (pintype "bidirectional"))
      (node (ref "U2") (pin "73") (pinfunction "VCC_ONE2_73") (pintype "bidirectional"))
    )
    (net (code "68") (name "Net-(U3-+IN)") (class "Default")
      (node (ref "C63") (pin "1") (pinfunction "1_1") (pintype "passive"))
      (node (ref "R22") (pin "2") (pinfunction "2_2") (pintype "passive"))
      (node (ref "U3") (pin "3") (pinfunction "+IN_3") (pintype "input"))
    )
    (net (code "69") (name "Net-(U3--IN)") (class "Default")
      (node (ref "C67") (pin "1") (pinfunction "1_1") (pintype "passive"))
      (node (ref "R24") (pin "2") (pinfunction "2_2") (pintype "passive"))
      (node (ref "U3") (pin "4") (pinfunction "-IN_4") (pintype "input"))
    )
    (net (code "70") (name "Net-(U3-OUT)") (class "Default")
      (node (ref "C65") (pin "+") (pinfunction "+_+") (pintype "passive"))
      (node (ref "C67") (pin "2") (pinfunction "2_2") (pintype "passive"))
      (node (ref "R28") (pin "2") (pinfunction "2_2") (pintype "passive"))
      (node (ref "U3") (pin "1") (pinfunction "OUT_1") (pintype "output"))
    )
    (net (code "71") (name "Net-(U4-CB)") (class "Default")
      (node (ref "C80") (pin "1") (pinfunction "1_1") (pintype "passive"))
      (node (ref "U4") (pin "1") (pinfunction "CB_1") (pintype "input"))
    )
    (net (code "72") (name "Net-(U4-FB)") (class "Default")
      (node (ref "R31") (pin "1") (pinfunction "1_1") (pintype "passive"))
      (node (ref "R35") (pin "2") (pinfunction "2_2") (pintype "passive"))
      (node (ref "U4") (pin "3") (pinfunction "FB_3") (pintype "input"))
    )
    (net (code "73") (name "Net-(U5-CB)") (class "Default")
      (node (ref "C81") (pin "1") (pinfunction "1_1") (pintype "passive"))
      (node (ref "U5") (pin "1") (pinfunction "CB_1") (pintype "input"))
    )
    (net (code "74") (name "Net-(U5-FB)") (class "Default")
      (node (ref "R32") (pin "1") (pinfunction "1_1") (pintype "passive"))
      (node (ref "R36") (pin "2") (pinfunction "2_2") (pintype "passive"))
      (node (ref "U5") (pin "3") (pinfunction "FB_3") (pintype "input"))
    )
    (net (code "75") (name "Net-(U6-+IN)") (class "Default")
      (node (ref "C92") (pin "1") (pinfunction "1_1") (pintype "passive"))
      (node (ref "R34") (pin "2") (pinfunction "2_2") (pintype "passive"))
      (node (ref "U6") (pin "3") (pinfunction "+IN_3") (pintype "input"))
    )
    (net (code "76") (name "Net-(U6--IN)") (class "Default")
      (node (ref "C98") (pin "1") (pinfunction "1_1") (pintype "passive"))
      (node (ref "R38") (pin "2") (pinfunction "2_2") (pintype "passive"))
      (node (ref "U6") (pin "4") (pinfunction "-IN_4") (pintype "input"))
    )
    (net (code "77") (name "Net-(U6-OUT)") (class "Default")
      (node (ref "C96") (pin "+") (pinfunction "+_+") (pintype "passive"))
      (node (ref "C98") (pin "2") (pinfunction "2_2") (pintype "passive"))
      (node (ref "R42") (pin "2") (pinfunction "2_2") (pintype "passive"))
      (node (ref "U6") (pin "1") (pinfunction "OUT_1") (pintype "output"))
    )
    (net (code "78") (name "Net-(U7-NP)") (class "Default")
      (node (ref "C105") (pin "1") (pinfunction "1_1") (pintype "passive"))
      (node (ref "U7") (pin "1") (pinfunction "NP_1") (pintype "input"))
    )
    (net (code "79") (name "Net-(U8-+IN)") (class "Default")
      (node (ref "R47") (pin "1") (pinfunction "1_1") (pintype "passive"))
      (node (ref "R52") (pin "2") (pinfunction "2_2") (pintype "passive"))
      (node (ref "U8") (pin "3") (pinfunction "+IN_3") (pintype "input"))
    )
    (net (code "80") (name "Net-(U8--IN)") (class "Default")
      (node (ref "C111") (pin "2") (pinfunction "2_2") (pintype "passive"))
      (node (ref "R53") (pin "1") (pinfunction "1_1") (pintype "passive"))
      (node (ref "R56") (pin "2") (pinfunction "2_2") (pintype "passive"))
      (node (ref "U8") (pin "4") (pinfunction "-IN_4") (pintype "input"))
    )
    (net (code "81") (name "Net-(U8-OUT)") (class "Default")
      (node (ref "C111") (pin "1") (pinfunction "1_1") (pintype "passive"))
      (node (ref "R50") (pin "1") (pinfunction "1_1") (pintype "passive"))
      (node (ref "R53") (pin "2") (pinfunction "2_2") (pintype "passive"))
      (node (ref "R54") (pin "1") (pinfunction "1_1") (pintype "passive"))
      (node (ref "U8") (pin "1") (pinfunction "OUT_1") (pintype "output"))
    )
    (net (code "82") (name "Net-(U9-ADJ+)") (class "Default")
      (node (ref "R45") (pin "1") (pinfunction "1_1") (pintype "passive"))
      (node (ref "R46") (pin "2") (pinfunction "2_2") (pintype "passive"))
      (node (ref "U9") (pin "18") (pinfunction "ADJ+_18") (pintype "tri_state"))
    )
    (net (code "83") (name "Net-(U9-ADJ-)") (class "Default")
      (node (ref "R48") (pin "1") (pinfunction "1_1") (pintype "passive"))
      (node (ref "R49") (pin "2") (pinfunction "2_2") (pintype "passive"))
      (node (ref "U9") (pin "7") (pinfunction "ADJ-_7") (pintype "tri_state"))
    )
    (net (code "84") (name "Net-(U9-BYP+)") (class "Default")
      (node (ref "C114") (pin "1") (pinfunction "1_1") (pintype "passive"))
      (node (ref "U9") (pin "17") (pinfunction "BYP+_17") (pintype "tri_state"))
    )
    (net (code "85") (name "Net-(U9-BYP-)") (class "Default")
      (node (ref "C115") (pin "1") (pinfunction "1_1") (pintype "passive"))
      (node (ref "U9") (pin "6") (pinfunction "BYP-_6") (pintype "power_in"))
    )
    (net (code "86") (name "Net-(U9-CBST+)") (class "Default")
      (node (ref "C113") (pin "1") (pinfunction "1_1") (pintype "passive"))
      (node (ref "U9") (pin "3") (pinfunction "CBST+_3") (pintype "passive"))
    )
    (net (code "87") (name "Net-(U9-CBST-)") (class "Default")
      (node (ref "C113") (pin "2") (pinfunction "2_2") (pintype "passive"))
      (node (ref "U9") (pin "2") (pinfunction "CBST-_2") (pintype "input"))
    )
    (net (code "88") (name "Net-(U9-CINV+)") (class "Default")
      (node (ref "C108") (pin "1") (pinfunction "1_1") (pintype "passive"))
      (node (ref "U9") (pin "12") (pinfunction "CINV+_12") (pintype "power_in"))
    )
    (net (code "89") (name "Net-(U9-CINV-)") (class "Default")
      (node (ref "C108") (pin "2") (pinfunction "2_2") (pintype "passive"))
      (node (ref "U9") (pin "10") (pinfunction "CINV-_10") (pintype "tri_state"))
    )
    (net (code "90") (name "Net-(U9-RT)") (class "Default")
      (node (ref "R57") (pin "2") (pinfunction "2_2") (pintype "passive"))
      (node (ref "U9") (pin "14") (pinfunction "RT_14") (pintype "output"))
    )
    (net (code "91") (name "Net-(U9-VIN_N)") (class "Default")
      (node (ref "C117") (pin "2") (pinfunction "2_2") (pintype "passive"))
      (node (ref "U9") (pin "13") (pinfunction "VIN_N_13") (pintype "power_in"))
      (node (ref "U9") (pin "20") (pinfunction "VOUT+_20") (pintype "tri_state"))
    )
    (net (code "92") (name "Net-(U9-VOUT-)") (class "Default")
      (node (ref "C122") (pin "2") (pinfunction "2_2") (pintype "passive"))
      (node (ref "U9") (pin "9") (pinfunction "VOUT-_9") (pintype "tri_state"))
    )
    (net (code "93") (name "Net-(U10-+IN)") (class "Default")
      (node (ref "R52") (pin "1") (pinfunction "1_1") (pintype "passive"))
      (node (ref "R56") (pin "1") (pinfunction "1_1") (pintype "passive"))
      (node (ref "R69") (pin "1") (pinfunction "1_1") (pintype "passive"))
      (node (ref "R74") (pin "1") (pinfunction "1_1") (pintype "passive"))
      (node (ref "U10") (pin "3") (pinfunction "+IN_3") (pintype "input"))
      (node (ref "U12") (pin "1") (pinfunction "OUT_1") (pintype "output"))
      (node (ref "U12") (pin "4") (pinfunction "-IN_4") (pintype "input"))
      (node (ref "U15") (pin "3") (pinfunction "+IN_3") (pintype "input"))
    )
    (net (code "94") (name "Net-(U10--IN)") (class "Default")
      (node (ref "C112") (pin "1") (pinfunction "1_1") (pintype "passive"))
      (node (ref "R54") (pin "2") (pinfunction "2_2") (pintype "passive"))
      (node (ref "R55") (pin "1") (pinfunction "1_1") (pintype "passive"))
      (node (ref "U10") (pin "4") (pinfunction "-IN_4") (pintype "input"))
    )
    (net (code "95") (name "Net-(U10-OUT)") (class "Default")
      (node (ref "C112") (pin "2") (pinfunction "2_2") (pintype "passive"))
      (node (ref "R55") (pin "2") (pinfunction "2_2") (pintype "passive"))
      (node (ref "R58") (pin "1") (pinfunction "1_1") (pintype "passive"))
      (node (ref "U10") (pin "1") (pinfunction "OUT_1") (pintype "output"))
    )
    (net (code "96") (name "Net-(U11-AINA+)") (class "Default")
      (node (ref "C116") (pin "2") (pinfunction "2_2") (pintype "passive"))
      (node (ref "R58") (pin "2") (pinfunction "2_2") (pintype "passive"))
      (node (ref "U11") (pin "17") (pinfunction "AINA+_17") (pintype "bidirectional"))
    )
    (net (code "97") (name "Net-(U11-AINA-)") (class "Default")
      (node (ref "C116") (pin "1") (pinfunction "1_1") (pintype "passive"))
      (node (ref "R50") (pin "2") (pinfunction "2_2") (pintype "passive"))
      (node (ref "U11") (pin "16") (pinfunction "AINA-_16") (pintype "bidirectional"))
    )
    (net (code "98") (name "Net-(U11-AINB+)") (class "Default")
      (node (ref "C132") (pin "1") (pinfunction "1_1") (pintype "passive"))
      (node (ref "R67") (pin "2") (pinfunction "2_2") (pintype "passive"))
      (node (ref "U11") (pin "18") (pinfunction "AINB+_18") (pintype "bidirectional"))
    )
    (net (code "99") (name "Net-(U11-AINB-)") (class "Default")
      (node (ref "C132") (pin "2") (pinfunction "2_2") (pintype "passive"))
      (node (ref "R75") (pin "2") (pinfunction "2_2") (pintype "passive"))
      (node (ref "U11") (pin "19") (pinfunction "AINB-_19") (pintype "bidirectional"))
    )
    (net (code "100") (name "Net-(U11-AOUTA+)") (class "Default")
      (node (ref "R21") (pin "1") (pinfunction "1_1") (pintype "passive"))
      (node (ref "U11") (pin "25") (pinfunction "AOUTA+_25") (pintype "bidirectional"))
    )
    (net (code "101") (name "Net-(U11-AOUTA-)") (class "Default")
      (node (ref "R23") (pin "1") (pinfunction "1_1") (pintype "passive"))
      (node (ref "U11") (pin "24") (pinfunction "AOUTA-_24") (pintype "bidirectional"))
    )
    (net (code "102") (name "Net-(U11-AOUTB+)") (class "Default")
      (node (ref "R37") (pin "1") (pinfunction "1_1") (pintype "passive"))
      (node (ref "U11") (pin "26") (pinfunction "AOUTB+_26") (pintype "bidirectional"))
    )
    (net (code "103") (name "Net-(U11-AOUTB-)") (class "Default")
      (node (ref "R33") (pin "1") (pinfunction "1_1") (pintype "passive"))
      (node (ref "U11") (pin "27") (pinfunction "AOUTB-_27") (pintype "bidirectional"))
    )
    (net (code "104") (name "Net-(U11-FILT+)") (class "Default")
      (node (ref "C120") (pin "1") (pinfunction "1_1") (pintype "passive"))
      (node (ref "C121") (pin "1") (pinfunction "1_1") (pintype "passive"))
      (node (ref "U11") (pin "22") (pinfunction "FILT+_22") (pintype "bidirectional"))
    )
    (net (code "105") (name "Net-(U11-I2S{slash}LJ)") (class "Default")
      (node (ref "R63") (pin "1") (pinfunction "1_1") (pintype "passive"))
      (node (ref "U11") (pin "13") (pinfunction "I2S/LJ_13") (pintype "bidirectional"))
      (node (ref "U2") (pin "44") (pinfunction "IO44_44") (pintype "bidirectional"))
    )
    (net (code "106") (name "Net-(U11-LRCLK)") (class "Default")
      (node (ref "U11") (pin "4") (pinfunction "LRCLK_4") (pintype "bidirectional"))
      (node (ref "U2") (pin "62") (pinfunction "IO62_62") (pintype "bidirectional"))
    )
    (net (code "107") (name "Net-(U11-M0)") (class "Default")
      (node (ref "R61") (pin "1") (pinfunction "1_1") (pintype "passive"))
      (node (ref "U11") (pin "11") (pinfunction "M0_11") (pintype "bidirectional"))
      (node (ref "U2") (pin "57") (pinfunction "IO57_57") (pintype "bidirectional"))
    )
    (net (code "108") (name "Net-(U11-M1)") (class "Default")
      (node (ref "R62") (pin "1") (pinfunction "1_1") (pintype "passive"))
      (node (ref "U11") (pin "12") (pinfunction "M1_12") (pintype "bidirectional"))
      (node (ref "U2") (pin "56") (pinfunction "IO56_56") (pintype "bidirectional"))
    )
    (net (code "109") (name "Net-(U11-MCLK)") (class "Default")
      (node (ref "U11") (pin "3") (pinfunction "MCLK_3") (pintype "bidirectional"))
      (node (ref "U2") (pin "64") (pinfunction "IO64_64") (pintype "bidirectional"))
    )
    (net (code "110") (name "Net-(U11-RST)") (class "Default")
      (node (ref "R64") (pin "1") (pinfunction "1_1") (pintype "passive"))
      (node (ref "U11") (pin "14") (pinfunction "RST_14") (pintype "bidirectional"))
      (node (ref "U2") (pin "43") (pinfunction "IO43_43") (pintype "bidirectional"))
    )
    (net (code "111") (name "Net-(U11-SCLK)") (class "Default")
      (node (ref "U11") (pin "5") (pinfunction "SCLK_5") (pintype "bidirectional"))
      (node (ref "U2") (pin "60") (pinfunction "IO60_60") (pintype "bidirectional"))
    )
    (net (code "112") (name "Net-(U11-SDIN)") (class "Default")
      (node (ref "U11") (pin "7") (pinfunction "SDIN_7") (pintype "bidirectional"))
      (node (ref "U2") (pin "58") (pinfunction "IO58_58") (pintype "bidirectional"))
    )
    (net (code "113") (name "Net-(U11-SDOUT(M{slash}S))") (class "Default")
      (node (ref "U11") (pin "6") (pinfunction "SDOUT(M/S)_6") (pintype "bidirectional"))
      (node (ref "U2") (pin "59") (pinfunction "IO59_59") (pintype "bidirectional"))
    )
    (net (code "114") (name "Net-(U12-+IN)") (class "Default")
      (node (ref "C125") (pin "1") (pinfunction "1_1") (pintype "passive"))
      (node (ref "R60") (pin "1") (pinfunction "1_1") (pintype "passive"))
      (node (ref "U12") (pin "3") (pinfunction "+IN_3") (pintype "input"))
    )
    (net (code "115") (name "Net-(U13-+IN)") (class "Default")
      (node (ref "R66") (pin "1") (pinfunction "1_1") (pintype "passive"))
      (node (ref "R69") (pin "2") (pinfunction "2_2") (pintype "passive"))
      (node (ref "U13") (pin "3") (pinfunction "+IN_3") (pintype "input"))
    )
    (net (code "116") (name "Net-(U13--IN)") (class "Default")
      (node (ref "C130") (pin "2") (pinfunction "2_2") (pintype "passive"))
      (node (ref "R71") (pin "1") (pinfunction "1_1") (pintype "passive"))
      (node (ref "R74") (pin "2") (pinfunction "2_2") (pintype "passive"))
      (node (ref "U13") (pin "4") (pinfunction "-IN_4") (pintype "input"))
    )
    (net (code "117") (name "Net-(U13-OUT)") (class "Default")
      (node (ref "C130") (pin "1") (pinfunction "1_1") (pintype "passive"))
      (node (ref "R67") (pin "1") (pinfunction "1_1") (pintype "passive"))
      (node (ref "R71") (pin "2") (pinfunction "2_2") (pintype "passive"))
      (node (ref "R72") (pin "1") (pinfunction "1_1") (pintype "passive"))
      (node (ref "U13") (pin "1") (pinfunction "OUT_1") (pintype "output"))
    )
    (net (code "118") (name "Net-(U14-OUT)") (class "Default")
      (node (ref "R70") (pin "1") (pinfunction "1_1") (pintype "passive"))
      (node (ref "U14") (pin "3") (pinfunction "OUT_3") (pintype "bidirectional"))
    )
    (net (code "119") (name "Net-(U15--IN)") (class "Default")
      (node (ref "C131") (pin "1") (pinfunction "1_1") (pintype "passive"))
      (node (ref "R72") (pin "2") (pinfunction "2_2") (pintype "passive"))
      (node (ref "R73") (pin "1") (pinfunction "1_1") (pintype "passive"))
      (node (ref "U15") (pin "4") (pinfunction "-IN_4") (pintype "input"))
    )
    (net (code "120") (name "Net-(U15-OUT)") (class "Default")
      (node (ref "C131") (pin "2") (pinfunction "2_2") (pintype "passive"))
      (node (ref "R73") (pin "2") (pinfunction "2_2") (pintype "passive"))
      (node (ref "R75") (pin "1") (pinfunction "1_1") (pintype "passive"))
      (node (ref "U15") (pin "1") (pinfunction "OUT_1") (pintype "output"))
    )
    (net (code "121") (name "Net-(U16-OUT)") (class "Default")
      (node (ref "R76") (pin "1") (pinfunction "1_1") (pintype "passive"))
      (node (ref "U16") (pin "3") (pinfunction "OUT_3") (pintype "bidirectional"))
    )
    (net (code "122") (name "Net-(X1-A)") (class "Default")
      (node (ref "R7") (pin "1") (pinfunction "1_1") (pintype "passive"))
      (node (ref "X1") (pin "A1") (pinfunction "A_A1") (pintype "passive"))
    )
    (net (code "123") (name "Net-(X1-A1)") (class "Default")
      (node (ref "R8") (pin "1") (pinfunction "1_1") (pintype "passive"))
      (node (ref "X1") (pin "A2") (pinfunction "A1_A2") (pintype "passive"))
    )
    (net (code "124") (name "Net-(X1-RCT)") (class "Default")
      (node (ref "C3") (pin "1") (pinfunction "1_1") (pintype "passive"))
      (node (ref "C42") (pin "2") (pinfunction "2_2") (pintype "passive"))
      (node (ref "C43") (pin "2") (pinfunction "2_2") (pintype "passive"))
      (node (ref "L4") (pin "1") (pinfunction "1_1") (pintype "passive"))
      (node (ref "U1") (pin "7") (pinfunction "VDDA_3.3_7") (pintype "input"))
      (node (ref "U1") (pin "8") (pinfunction "VDDA_3.3_8") (pintype "input"))
      (node (ref "X1") (pin "2") (pinfunction "TCT_2") (pintype "passive"))
      (node (ref "X1") (pin "5") (pinfunction "RCT_5") (pintype "passive"))
    )
    (net (code "125") (name "Net-(X3-1)") (class "Default")
      (node (ref "C66") (pin "-") (pinfunction "-_-") (pintype "passive"))
      (node (ref "R27") (pin "2") (pinfunction "2_2") (pintype "passive"))
      (node (ref "X3") (pin "S1") (pinfunction "1_S1") (pintype "passive"))
    )
    (net (code "126") (name "Net-(X4-1)") (class "Default")
      (node (ref "C97") (pin "-") (pinfunction "-_-") (pintype "passive"))
      (node (ref "R41") (pin "2") (pinfunction "2_2") (pintype "passive"))
      (node (ref "X4") (pin "S1") (pinfunction "1_S1") (pintype "passive"))
    )
    (net (code "127") (name "Net-(X5-1)") (class "Default")
      (node (ref "C107") (pin "-") (pinfunction "-_-") (pintype "passive"))
      (node (ref "R51") (pin "2") (pinfunction "2_2") (pintype "passive"))
      (node (ref "X5") (pin "S1") (pinfunction "1_S1") (pintype "passive"))
    )
    (net (code "128") (name "Net-(X7-1)") (class "Default")
      (node (ref "C128") (pin "-") (pinfunction "-_-") (pintype "passive"))
      (node (ref "R68") (pin "2") (pinfunction "2_2") (pintype "passive"))
      (node (ref "X7") (pin "S1") (pinfunction "1_S1") (pintype "passive"))
    )
    (net (code "129") (name "V_COM") (class "Default")
      (node (ref "C123") (pin "2") (pinfunction "2_2") (pintype "passive"))
      (node (ref "C124") (pin "2") (pinfunction "2_2") (pintype "passive"))
      (node (ref "R60") (pin "2") (pinfunction "2_2") (pintype "passive"))
      (node (ref "U11") (pin "15") (pinfunction "VCOM_15") (pintype "bidirectional"))
    )
    (net (code "130") (name "V_IN") (class "Default")
      (node (ref "C90") (pin "1") (pinfunction "1_1") (pintype "passive"))
      (node (ref "C91") (pin "1") (pinfunction "1_1") (pintype "passive"))
      (node (ref "D3") (pin "1") (pinfunction "C_1") (pintype "passive"))
      (node (ref "Q1") (pin "2") (pinfunction "S_2") (pintype "passive"))
      (node (ref "U4") (pin "4") (pinfunction "SHDN_4") (pintype "bidirectional"))
      (node (ref "U4") (pin "5") (pinfunction "VIN_5") (pintype "bidirectional"))
      (node (ref "U5") (pin "4") (pinfunction "SHDN_4") (pintype "bidirectional"))
      (node (ref "U5") (pin "5") (pinfunction "VIN_5") (pintype "bidirectional"))
    )
    (net (code "131") (name "unconnected-(U1-CRS{slash}CONFIG1-Pad41)") (class "Default")
      (node (ref "U1") (pin "41") (pinfunction "CRS/CONFIG1_41") (pintype "bidirectional"))
    )
    (net (code "132") (name "unconnected-(U1-INTRP-Pad32)") (class "Default")
      (node (ref "U1") (pin "32") (pinfunction "INTRP_32") (pintype "output"))
    )
    (net (code "133") (name "unconnected-(U1-NC-Pad44)") (class "Default")
      (node (ref "U1") (pin "44") (pinfunction "NC_44") (pintype "no_connect"))
    )
    (net (code "134") (name "unconnected-(U1-NC-Pad45)") (class "Default")
      (node (ref "U1") (pin "45") (pinfunction "NC_45") (pintype "no_connect"))
    )
    (net (code "135") (name "unconnected-(U1-NC-Pad46)") (class "Default")
      (node (ref "U1") (pin "46") (pinfunction "NC_46") (pintype "no_connect"))
    )
    (net (code "136") (name "unconnected-(U1-NC-Pad48)") (class "Default")
      (node (ref "U1") (pin "48") (pinfunction "NC_48") (pintype "no_connect"))
    )
    (net (code "137") (name "unconnected-(U1-RXD2{slash}PHYAD1-Pad21)") (class "Default")
      (node (ref "U1") (pin "21") (pinfunction "RXD2/PHYAD1_21") (pintype "bidirectional"))
    )
    (net (code "138") (name "unconnected-(U1-RXD3{slash}PHYAD0-Pad20)") (class "Default")
      (node (ref "U1") (pin "20") (pinfunction "RXD3/PHYAD0_20") (pintype "bidirectional"))
    )
    (net (code "139") (name "unconnected-(U1-TXC-Pad33)") (class "Default")
      (node (ref "U1") (pin "33") (pinfunction "TXC_33") (pintype "bidirectional"))
    )
    (net (code "140") (name "unconnected-(U1-TXD2-Pad38)") (class "Default")
      (node (ref "U1") (pin "38") (pinfunction "TXD2_38") (pintype "input"))
    )
    (net (code "141") (name "unconnected-(U1-TXD3-Pad39)") (class "Default")
      (node (ref "U1") (pin "39") (pinfunction "TXD3_39") (pintype "input"))
    )
    (net (code "142") (name "unconnected-(U1-XO-Pad14)") (class "Default")
      (node (ref "U1") (pin "14") (pinfunction "XO_14") (pintype "output"))
    )
    (net (code "143") (name "unconnected-(U2A-IO6-Pad6)") (class "Default")
      (node (ref "U2") (pin "6") (pinfunction "IO6_6") (pintype "bidirectional"))
    )
    (net (code "144") (name "unconnected-(U2A-IO7-Pad7)") (class "Default")
      (node (ref "U2") (pin "7") (pinfunction "IO7_7") (pintype "bidirectional"))
    )
    (net (code "145") (name "unconnected-(U2A-IO8-Pad8)") (class "Default")
      (node (ref "U2") (pin "8") (pinfunction "IO8_8") (pintype "bidirectional"))
    )
    (net (code "146") (name "unconnected-(U2A-IO10-Pad10)") (class "Default")
      (node (ref "U2") (pin "10") (pinfunction "IO10_10") (pintype "bidirectional"))
    )
    (net (code "147") (name "unconnected-(U2A-IO11-Pad11)") (class "Default")
      (node (ref "U2") (pin "11") (pinfunction "IO11_11") (pintype "bidirectional"))
    )
    (net (code "148") (name "unconnected-(U2A-IO12-Pad12)") (class "Default")
      (node (ref "U2") (pin "12") (pinfunction "IO12_12") (pintype "bidirectional"))
    )
    (net (code "149") (name "unconnected-(U2A-IO13-Pad13)") (class "Default")
      (node (ref "U2") (pin "13") (pinfunction "IO13_13") (pintype "bidirectional"))
    )
    (net (code "150") (name "unconnected-(U2A-IO14-Pad14)") (class "Default")
      (node (ref "U2") (pin "14") (pinfunction "IO14_14") (pintype "bidirectional"))
    )
    (net (code "151") (name "unconnected-(U2A-IO21-Pad21)") (class "Default")
      (node (ref "U2") (pin "21") (pinfunction "IO21_21") (pintype "bidirectional"))
    )
    (net (code "152") (name "unconnected-(U2A-IO22-Pad22)") (class "Default")
      (node (ref "U2") (pin "22") (pinfunction "IO22_22") (pintype "bidirectional"))
    )
    (net (code "153") (name "unconnected-(U2A-IO24-Pad24)") (class "Default")
      (node (ref "U2") (pin "24") (pinfunction "IO24_24") (pintype "bidirectional"))
    )
    (net (code "154") (name "unconnected-(U2A-IO25-Pad25)") (class "Default")
      (node (ref "U2") (pin "25") (pinfunction "IO25_25") (pintype "bidirectional"))
    )
    (net (code "155") (name "unconnected-(U2A-VREFB1N0-Pad17)") (class "Default")
      (node (ref "U2") (pin "17") (pinfunction "VREFB1N0_17") (pintype "bidirectional"))
    )
    (net (code "156") (name "unconnected-(U2B-IO26-Pad26)") (class "Default")
      (node (ref "U2") (pin "26") (pinfunction "IO26_26") (pintype "bidirectional"))
    )
    (net (code "157") (name "unconnected-(U2B-IO28-Pad28)") (class "Default")
      (node (ref "U2") (pin "28") (pinfunction "IO28_28") (pintype "bidirectional"))
    )
    (net (code "158") (name "unconnected-(U2B-IO32-Pad32)") (class "Default")
      (node (ref "U2") (pin "32") (pinfunction "IO32_32") (pintype "bidirectional"))
    )
    (net (code "159") (name "unconnected-(U2B-IO33-Pad33)") (class "Default")
      (node (ref "U2") (pin "33") (pinfunction "IO33_33") (pintype "bidirectional"))
    )
    (net (code "160") (name "unconnected-(U2B-IO38-Pad38)") (class "Default")
      (node (ref "U2") (pin "38") (pinfunction "IO38_38") (pintype "bidirectional"))
    )
    (net (code "161") (name "unconnected-(U2B-IO39-Pad39)") (class "Default")
      (node (ref "U2") (pin "39") (pinfunction "IO39_39") (pintype "bidirectional"))
    )
    (net (code "162") (name "unconnected-(U2B-IO41-Pad41)") (class "Default")
      (node (ref "U2") (pin "41") (pinfunction "IO41_41") (pintype "bidirectional"))
    )
    (net (code "163") (name "unconnected-(U2B-IO45-Pad45)") (class "Default")
      (node (ref "U2") (pin "45") (pinfunction "IO45_45") (pintype "bidirectional"))
    )
    (net (code "164") (name "unconnected-(U2B-IO46-Pad46)") (class "Default")
      (node (ref "U2") (pin "46") (pinfunction "IO46_46") (pintype "bidirectional"))
    )
    (net (code "165") (name "unconnected-(U2B-IO47-Pad47)") (class "Default")
      (node (ref "U2") (pin "47") (pinfunction "IO47_47") (pintype "bidirectional"))
    )
    (net (code "166") (name "unconnected-(U2B-IO50-Pad50)") (class "Default")
      (node (ref "U2") (pin "50") (pinfunction "IO50_50") (pintype "bidirectional"))
    )
    (net (code "167") (name "unconnected-(U2B-IO52-Pad52)") (class "Default")
      (node (ref "U2") (pin "52") (pinfunction "IO52_52") (pintype "bidirectional"))
    )
    (net (code "168") (name "unconnected-(U2B-IO54-Pad54)") (class "Default")
      (node (ref "U2") (pin "54") (pinfunction "IO54_54") (pintype "bidirectional"))
    )
    (net (code "169") (name "unconnected-(U2B-IO55-Pad55)") (class "Default")
      (node (ref "U2") (pin "55") (pinfunction "IO55_55") (pintype "bidirectional"))
    )
    (net (code "170") (name "unconnected-(U2B-IO65-Pad65)") (class "Default")
      (node (ref "U2") (pin "65") (pinfunction "IO65_65") (pintype "bidirectional"))
    )
    (net (code "171") (name "unconnected-(U2B-IO66-Pad66)") (class "Default")
      (node (ref "U2") (pin "66") (pinfunction "IO66_66") (pintype "bidirectional"))
    )
    (net (code "172") (name "unconnected-(U2B-IO69-Pad69)") (class "Default")
      (node (ref "U2") (pin "69") (pinfunction "IO69_69") (pintype "bidirectional"))
    )
    (net (code "173") (name "unconnected-(U2B-IO70-Pad70)") (class "Default")
      (node (ref "U2") (pin "70") (pinfunction "IO70_70") (pintype "bidirectional"))
    )
    (net (code "174") (name "unconnected-(U2B-VREFB2N0-Pad30)") (class "Default")
      (node (ref "U2") (pin "30") (pinfunction "VREFB2N0_30") (pintype "bidirectional"))
    )
    (net (code "175") (name "unconnected-(U2B-VREFB3N0-Pad48)") (class "Default")
      (node (ref "U2") (pin "48") (pinfunction "VREFB3N0_48") (pintype "bidirectional"))
    )
    (net (code "176") (name "unconnected-(U2B-VREFB4N0-Pad61)") (class "Default")
      (node (ref "U2") (pin "61") (pinfunction "VREFB4N0_61") (pintype "bidirectional"))
    )
    (net (code "177") (name "unconnected-(U2C-IO81-Pad81)") (class "Default")
      (node (ref "U2") (pin "81") (pinfunction "IO81_81") (pintype "bidirectional"))
    )
    (net (code "178") (name "unconnected-(U2C-IO84-Pad84)") (class "Default")
      (node (ref "U2") (pin "84") (pinfunction "IO84_84") (pintype "bidirectional"))
    )
    (net (code "179") (name "unconnected-(U2C-IO85-Pad85)") (class "Default")
      (node (ref "U2") (pin "85") (pinfunction "IO85_85") (pintype "bidirectional"))
    )
    (net (code "180") (name "unconnected-(U2C-IO91-Pad91)") (class "Default")
      (node (ref "U2") (pin "91") (pinfunction "IO91_91") (pintype "bidirectional"))
    )
    (net (code "181") (name "unconnected-(U2C-IO92-Pad92)") (class "Default")
      (node (ref "U2") (pin "92") (pinfunction "IO92_92") (pintype "bidirectional"))
    )
    (net (code "182") (name "unconnected-(U2C-IO93-Pad93)") (class "Default")
      (node (ref "U2") (pin "93") (pinfunction "IO93_93") (pintype "bidirectional"))
    )
    (net (code "183") (name "unconnected-(U2C-IO96-Pad96)") (class "Default")
      (node (ref "U2") (pin "96") (pinfunction "IO96_96") (pintype "bidirectional"))
    )
    (net (code "184") (name "unconnected-(U2C-IO99-Pad99)") (class "Default")
      (node (ref "U2") (pin "99") (pinfunction "IO99_99") (pintype "bidirectional"))
    )
    (net (code "185") (name "unconnected-(U2C-IO100-Pad100)") (class "Default")
      (node (ref "U2") (pin "100") (pinfunction "IO100_100") (pintype "bidirectional"))
    )
    (net (code "186") (name "unconnected-(U2C-IO101-Pad101)") (class "Default")
      (node (ref "U2") (pin "101") (pinfunction "IO101_101") (pintype "bidirectional"))
    )
    (net (code "187") (name "unconnected-(U2C-IO102-Pad102)") (class "Default")
      (node (ref "U2") (pin "102") (pinfunction "IO102_102") (pintype "bidirectional"))
    )
    (net (code "188") (name "unconnected-(U2C-IO105-Pad105)") (class "Default")
      (node (ref "U2") (pin "105") (pinfunction "IO105_105") (pintype "bidirectional"))
    )
    (net (code "189") (name "unconnected-(U2C-IO106-Pad106)") (class "Default")
      (node (ref "U2") (pin "106") (pinfunction "IO106_106") (pintype "bidirectional"))
    )
    (net (code "190") (name "unconnected-(U2C-VREFB5N0-Pad80)") (class "Default")
      (node (ref "U2") (pin "80") (pinfunction "VREFB5N0_80") (pintype "bidirectional"))
    )
    (net (code "191") (name "unconnected-(U2C-VREFB6N0-Pad97)") (class "Default")
      (node (ref "U2") (pin "97") (pinfunction "VREFB6N0_97") (pintype "bidirectional"))
    )
    (net (code "192") (name "unconnected-(U2D-CRC_ERROR-Pad134)") (class "Default")
      (node (ref "U2") (pin "134") (pinfunction "CRC_ERROR_134") (pintype "bidirectional"))
    )
    (net (code "193") (name "unconnected-(U2D-DEV_OE-Pad122)") (class "Default")
      (node (ref "U2") (pin "122") (pinfunction "DEV_OE_122") (pintype "bidirectional"))
    )
    (net (code "194") (name "unconnected-(U2D-IO111-Pad111)") (class "Default")
      (node (ref "U2") (pin "111") (pinfunction "IO111_111") (pintype "bidirectional"))
    )
    (net (code "195") (name "unconnected-(U2D-IO113-Pad113)") (class "Default")
      (node (ref "U2") (pin "113") (pinfunction "IO113_113") (pintype "bidirectional"))
    )
    (net (code "196") (name "unconnected-(U2D-IO114-Pad114)") (class "Default")
      (node (ref "U2") (pin "114") (pinfunction "IO114_114") (pintype "bidirectional"))
    )
    (net (code "197") (name "unconnected-(U2D-IO118-Pad118)") (class "Default")
      (node (ref "U2") (pin "118") (pinfunction "IO118_118") (pintype "bidirectional"))
    )
    (net (code "198") (name "unconnected-(U2D-IO119-Pad119)") (class "Default")
      (node (ref "U2") (pin "119") (pinfunction "IO119_119") (pintype "bidirectional"))
    )
    (net (code "199") (name "unconnected-(U2D-IO120-Pad120)") (class "Default")
      (node (ref "U2") (pin "120") (pinfunction "IO120_120") (pintype "bidirectional"))
    )
    (net (code "200") (name "unconnected-(U2D-IO124-Pad124)") (class "Default")
      (node (ref "U2") (pin "124") (pinfunction "IO124_124") (pintype "bidirectional"))
    )
    (net (code "201") (name "unconnected-(U2D-IO127-Pad127)") (class "Default")
      (node (ref "U2") (pin "127") (pinfunction "IO127_127") (pintype "bidirectional"))
    )
    (net (code "202") (name "unconnected-(U2D-IO130-Pad130)") (class "Default")
      (node (ref "U2") (pin "130") (pinfunction "IO130_130") (pintype "bidirectional"))
    )
    (net (code "203") (name "unconnected-(U2D-IO131-Pad131)") (class "Default")
      (node (ref "U2") (pin "131") (pinfunction "IO131_131") (pintype "bidirectional"))
    )
    (net (code "204") (name "unconnected-(U2D-IO132-Pad132)") (class "Default")
      (node (ref "U2") (pin "132") (pinfunction "IO132_132") (pintype "bidirectional"))
    )
    (net (code "205") (name "unconnected-(U2D-IO135-Pad135)") (class "Default")
      (node (ref "U2") (pin "135") (pinfunction "IO135_135") (pintype "bidirectional"))
    )
    (net (code "206") (name "unconnected-(U2D-IO140-Pad140)") (class "Default")
      (node (ref "U2") (pin "140") (pinfunction "IO140_140") (pintype "bidirectional"))
    )
    (net (code "207") (name "unconnected-(U2D-IO141-Pad141)") (class "Default")
      (node (ref "U2") (pin "141") (pinfunction "IO141_141") (pintype "bidirectional"))
    )
    (net (code "208") (name "unconnected-(U2D-VREFB7N0-Pad112)") (class "Default")
      (node (ref "U2") (pin "112") (pinfunction "VREFB7N0_112") (pintype "bidirectional"))
    )
    (net (code "209") (name "unconnected-(U2D-VREFB8N0-Pad123)") (class "Default")
      (node (ref "U2") (pin "123") (pinfunction "VREFB8N0_123") (pintype "bidirectional"))
    )
    (net (code "210") (name "unconnected-(U2E-ADC_VREF-Pad5)") (class "Default")
      (node (ref "U2") (pin "5") (pinfunction "ADC_VREF_5") (pintype "bidirectional"))
    )
    (net (code "211") (name "unconnected-(U9-NC1-Pad1)") (class "Default")
      (node (ref "U9") (pin "1") (pinfunction "NC1_1") (pintype "input"))
    )
    (net (code "212") (name "unconnected-(U9-NC2-Pad11)") (class "Default")
      (node (ref "U9") (pin "11") (pinfunction "NC2_11") (pintype "input"))
    )
    (net (code "213") (name "unconnected-(U11-AMUTEC-Pad23)") (class "Default")
      (node (ref "U11") (pin "23") (pinfunction "AMUTEC_23") (pintype "bidirectional"))
    )
    (net (code "214") (name "unconnected-(U11-BMUTEC-Pad28)") (class "Default")
      (node (ref "U11") (pin "28") (pinfunction "BMUTEC_28") (pintype "bidirectional"))
    )
    (net (code "215") (name "unconnected-(U11-XTO-Pad1)") (class "Default")
      (node (ref "U11") (pin "1") (pinfunction "XTO_1") (pintype "bidirectional"))
    )
    (net (code "216") (name "unconnected-(U14-EN-Pad1)") (class "Default")
      (node (ref "U14") (pin "1") (pinfunction "EN_1") (pintype "bidirectional"))
    )
    (net (code "217") (name "unconnected-(U16-EN-Pad1)") (class "Default")
      (node (ref "U16") (pin "1") (pinfunction "EN_1") (pintype "bidirectional"))
    )
    (net (code "218") (name "unconnected-(X1-C_GND-Pad8)") (class "Default")
      (node (ref "X1") (pin "8") (pinfunction "C_GND_8") (pintype "passive"))
    )
    (net (code "219") (name "unconnected-(X1-NC-Pad7)") (class "Default")
      (node (ref "X1") (pin "7") (pinfunction "NC_7") (pintype "passive"))
    )
    (net (code "220") (name "unconnected-(X1-PadS1)") (class "Default")
      (node (ref "X1") (pin "S1") (pinfunction "S1_S1") (pintype "passive"))
    )
    (net (code "221") (name "unconnected-(X1-PadS2)") (class "Default")
      (node (ref "X1") (pin "S2") (pinfunction "S2_S2") (pintype "passive"))
    )
    (net (code "222") (name "unconnected-(X2G-KL-Pad6)") (class "Default")
      (node (ref "X2") (pin "6") (pinfunction "KL_6") (pintype "passive"))
    )
    (net (code "223") (name "unconnected-(X2H-KL-Pad7)") (class "Default")
      (node (ref "X2") (pin "7") (pinfunction "KL_7") (pintype "passive"))
    )
  )
)
